# Display_CPu.net
KiCad netlist of a schematic drawn in Altium Designer
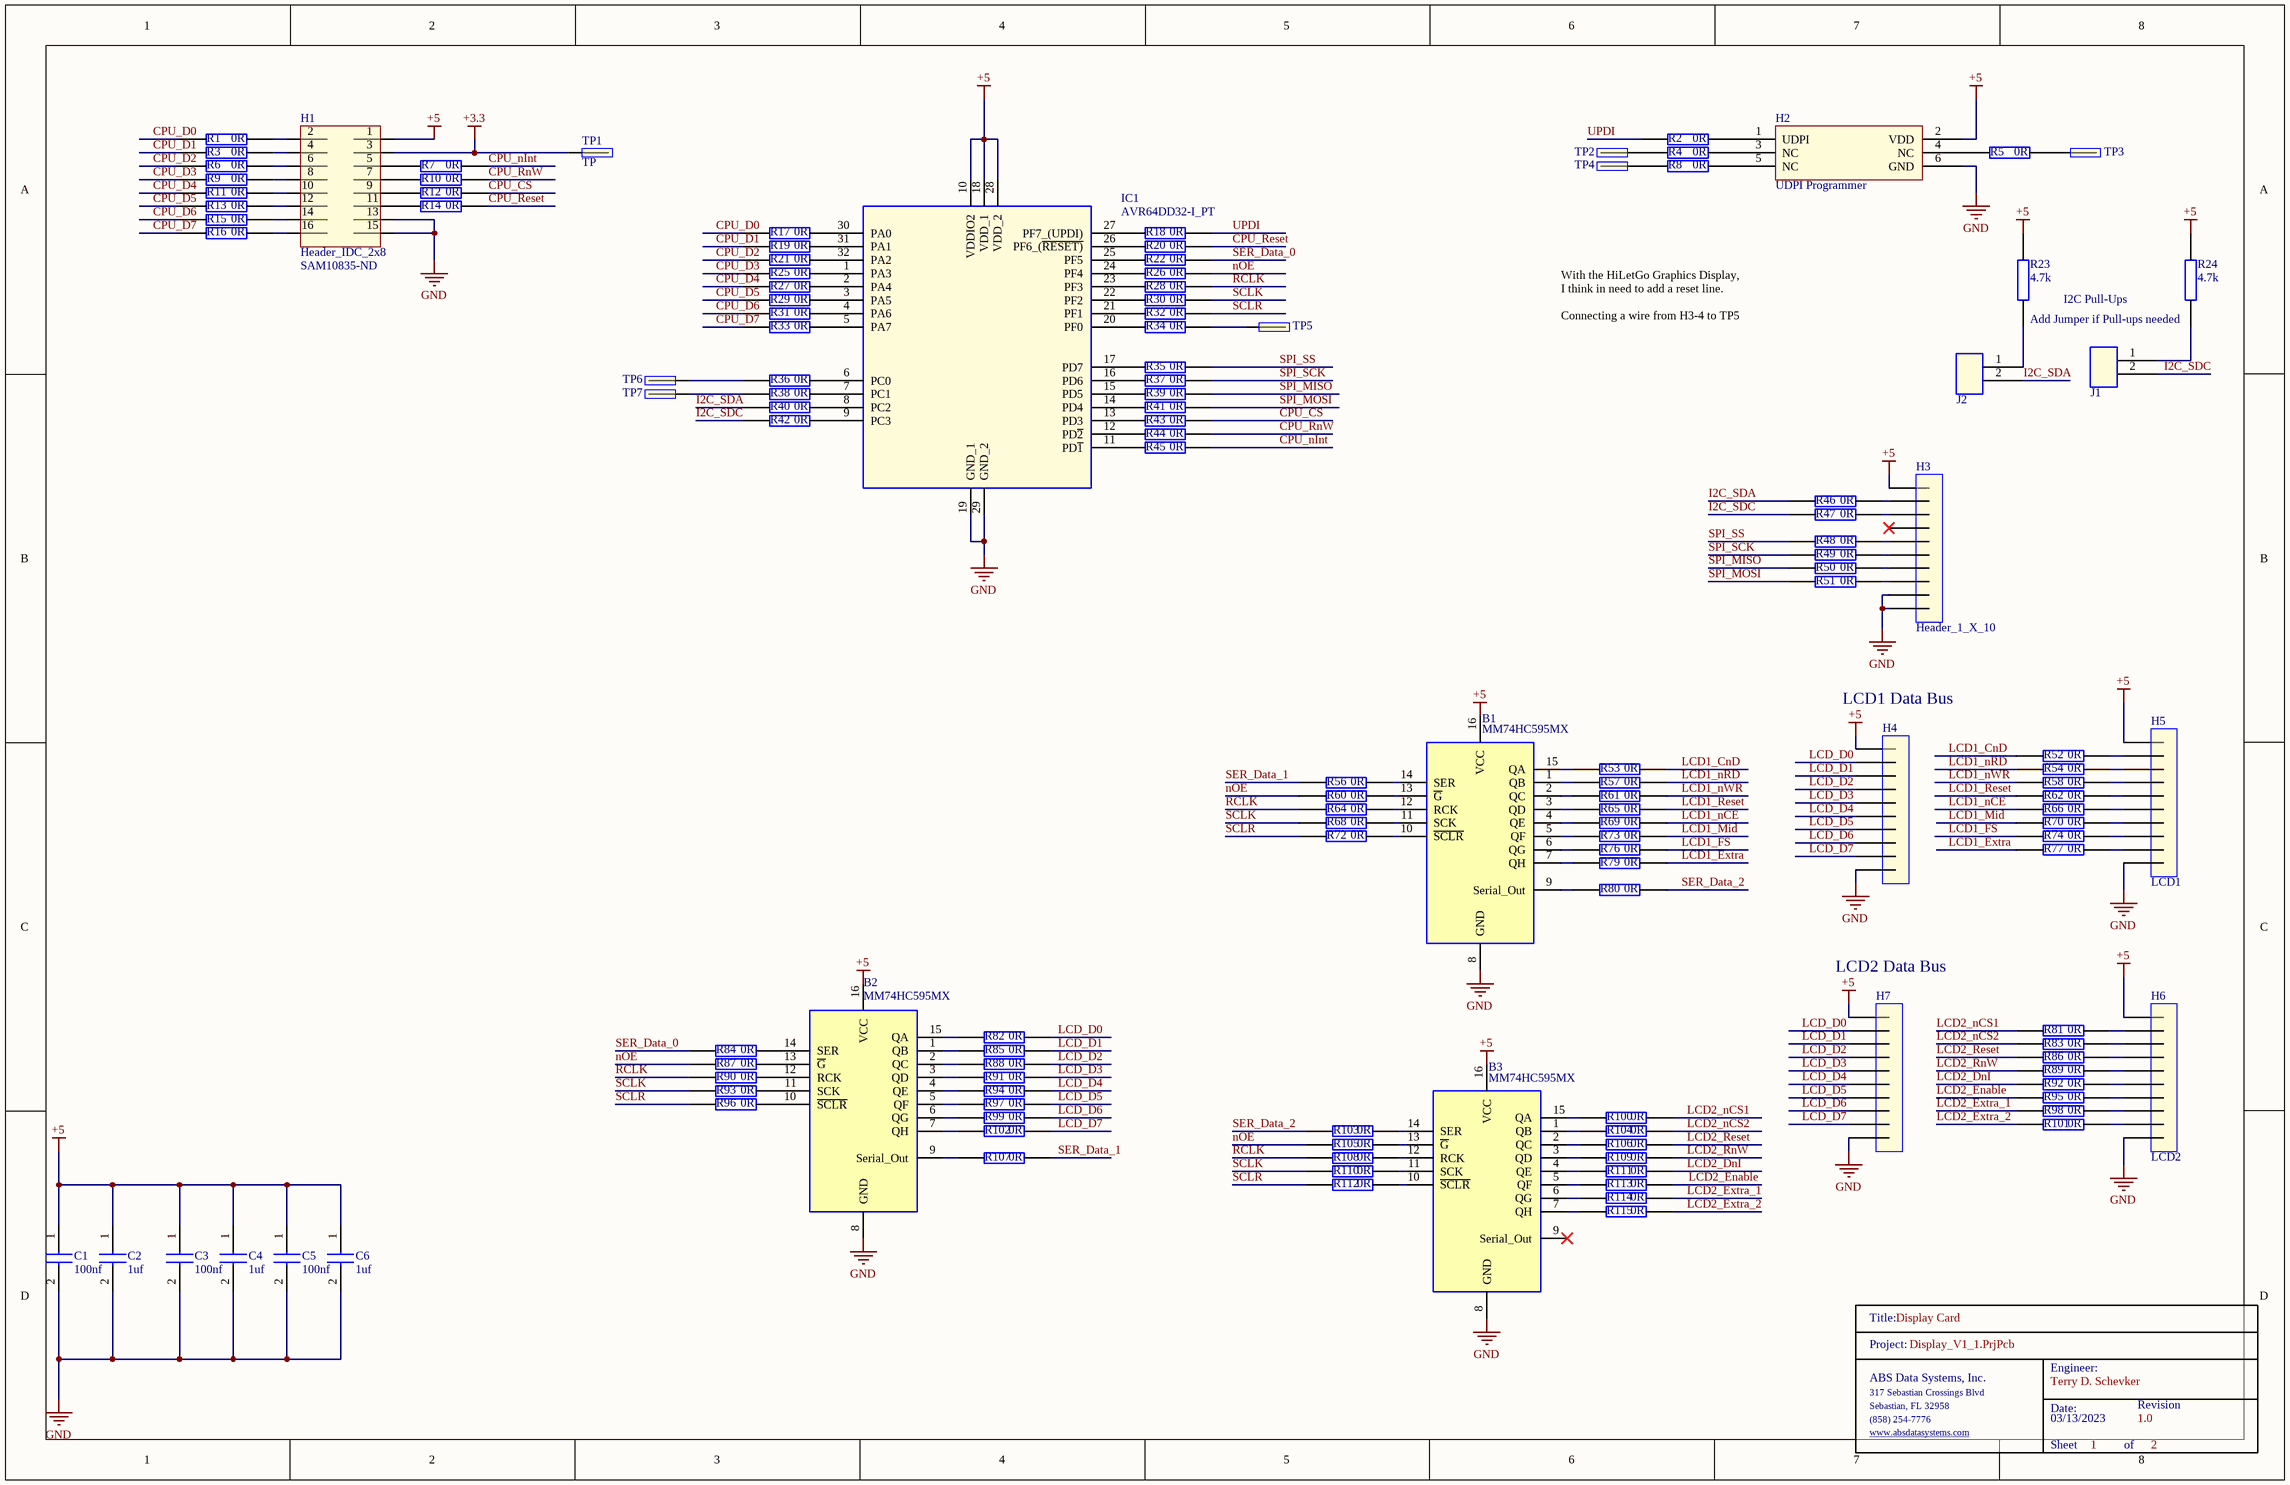
[diagram p0: Display_CPu.SchDoc]

(export (version "E")
  (design (tool "Eeschema 10.0.6"))
  (components
    (comp (ref "B1")
      (value "MM74HC595MX")
      (footprint "SOIC127P600X175-16N")
      (description "Shift Register HS 8 Bit CMOS SOIC16")
      (fields (field (name "MOUSER PART NUMBER") "512-MM74HC595MX"))
      (libsource (lib "SemiConductors") (part "MM74HC595MX"))
    )
    (comp (ref "B2")
      (value "MM74HC595MX")
      (footprint "SOIC127P600X175-16N")
      (description "Shift Register HS 8 Bit CMOS SOIC16")
      (fields (field (name "MOUSER PART NUMBER") "512-MM74HC595MX"))
      (libsource (lib "SemiConductors") (part "MM74HC595MX"))
    )
    (comp (ref "B3")
      (value "MM74HC595MX")
      (footprint "SOIC127P600X175-16N")
      (description "Shift Register HS 8 Bit CMOS SOIC16")
      (fields (field (name "MOUSER PART NUMBER") "512-MM74HC595MX"))
      (libsource (lib "SemiConductors") (part "MM74HC595MX"))
    )
    (comp (ref "C1")
      (value "100nf")
      (footprint "0603")
      (description "Samsung Electro-Mechanics 0603 100nf")
      (libsource (lib "Capacitors") (part "CL10B104JB8NNNC"))
    )
    (comp (ref "C2")
      (value "1uf")
      (footprint "0603")
      (description "Samsung Electro-Mechanics 0603 1uf")
      (libsource (lib "Capacitors") (part "CL10B105KA8NNNL"))
    )
    (comp (ref "C3")
      (value "100nf")
      (footprint "0603")
      (description "Samsung Electro-Mechanics 0603 100nf")
      (libsource (lib "Capacitors") (part "CL10B104JB8NNNC"))
    )
    (comp (ref "C4")
      (value "1uf")
      (footprint "0603")
      (description "Samsung Electro-Mechanics 0603 1uf")
      (libsource (lib "Capacitors") (part "CL10B105KA8NNNL"))
    )
    (comp (ref "C5")
      (value "100nf")
      (footprint "0603")
      (description "Samsung Electro-Mechanics 0603 100nf")
      (libsource (lib "Capacitors") (part "CL10B104JB8NNNC"))
    )
    (comp (ref "C6")
      (value "1uf")
      (footprint "0603")
      (description "Samsung Electro-Mechanics 0603 1uf")
      (libsource (lib "Capacitors") (part "CL10B105KA8NNNL"))
    )
    (comp (ref "H1")
      (value "Header_IDC_2x8")
      (footprint "HEADER16")
      (description "16 Pin 2x8 Through Hold IDC Connector")
      (fields
        (field (name "MANUFACTURER") "Samtec")
        (field (name "MANUFACTURER PART NUMBER") "TST-108-01-G-D")
        (field (name "SUPPLIER PART NUMBER 1") "SAM10835-ND")
      )
      (libsource (lib "Misc") (part "Header_IDC_2x8"))
    )
    (comp (ref "H2")
      (value "UDPI Programmer")
      (footprint "HDR2X3")
      (description "6 Pin 2X3 Through Hole Header")
      (libsource (lib "Misc") (part "UDPI Programmer"))
    )
    (comp (ref "H3")
      (value "Header_1_X_10")
      (footprint "TP_1X10")
      (fields
        (field (name "MANUFACTURER") "Samtec")
        (field (name "MANUFACTURER PART NUMBER") "TST-105-01-G-D")
      )
      (libsource (lib "Misc") (part "Header_1_X_10"))
    )
    (comp (ref "H4")
      (value "Header_1_X_10")
      (footprint "TP_1X10")
      (fields
        (field (name "MANUFACTURER") "Samtec")
        (field (name "MANUFACTURER PART NUMBER") "TST-105-01-G-D")
      )
      (libsource (lib "Misc") (part "Header_1_X_10"))
    )
    (comp (ref "H5")
      (value "LCD1")
      (footprint "TP_1X10")
      (fields
        (field (name "MANUFACTURER") "Samtec")
        (field (name "MANUFACTURER PART NUMBER") "TST-105-01-G-D")
      )
      (libsource (lib "Misc") (part "Header_1_X_10"))
    )
    (comp (ref "H6")
      (value "LCD2")
      (footprint "TP_1X10")
      (fields
        (field (name "MANUFACTURER") "Samtec")
        (field (name "MANUFACTURER PART NUMBER") "TST-105-01-G-D")
      )
      (libsource (lib "Misc") (part "Header_1_X_10"))
    )
    (comp (ref "H7")
      (value "Header_1_X_10")
      (footprint "TP_1X10")
      (fields
        (field (name "MANUFACTURER") "Samtec")
        (field (name "MANUFACTURER PART NUMBER") "TST-105-01-G-D")
      )
      (libsource (lib "Misc") (part "Header_1_X_10"))
    )
    (comp (ref "IC1")
      (value "AVR64DD32-I_PT")
      (footprint "CPU_Memory:QFP80P900X900X120-32N")
      (description "Integrated Circuit")
      (fields (field (name "MANUFACTURER_PART_NUMBER") "AVR64DD32-I/PT ¦ MULTI-VOLTAGE I/O"))
      (libsource (lib "CPU_Memory") (part "AVR64DD32-I_PT"))
    )
    (comp (ref "J1")
      (value "Jumper")
      (footprint "Jumper")
      (description "16 Pin 3x8 Through Hold Jumprts")
      (fields
        (field (name "MANUFACTURER") "Samtec")
        (field (name "MANUFACTURER PART NUMBER") "TST-108-01-G-D")
      )
      (libsource (lib "Misc") (part "Jumper"))
    )
    (comp (ref "J2")
      (value "Jumper")
      (footprint "Jumper")
      (description "16 Pin 3x8 Through Hold Jumprts")
      (fields
        (field (name "MANUFACTURER") "Samtec")
        (field (name "MANUFACTURER PART NUMBER") "TST-108-01-G-D")
      )
      (libsource (lib "Misc") (part "Jumper"))
    )
    (comp (ref "R1")
      (value "0R")
      (footprint "0603")
      (description "YAGEO 0603 0 ohm")
      (fields
        (field (name "MOUSER PART NUMBER") "603-RC0603JR-070RL")
        (field (name "MANUFACTURER_PART_NUMBER") "RC0603JR-070RL")
      )
      (libsource (lib "Resistors") (part "RC0603JR-070RL"))
    )
    (comp (ref "R2")
      (value "0R")
      (footprint "0603")
      (description "YAGEO 0603 0 ohm")
      (fields
        (field (name "MOUSER PART NUMBER") "603-RC0603JR-070RL")
        (field (name "MANUFACTURER_PART_NUMBER") "RC0603JR-070RL")
      )
      (libsource (lib "Resistors") (part "RC0603JR-070RL"))
    )
    (comp (ref "R3")
      (value "0R")
      (footprint "0603")
      (description "YAGEO 0603 0 ohm")
      (fields
        (field (name "MOUSER PART NUMBER") "603-RC0603JR-070RL")
        (field (name "MANUFACTURER_PART_NUMBER") "RC0603JR-070RL")
      )
      (libsource (lib "Resistors") (part "RC0603JR-070RL"))
    )
    (comp (ref "R4")
      (value "0R")
      (footprint "0603")
      (description "YAGEO 0603 0 ohm")
      (fields
        (field (name "MOUSER PART NUMBER") "603-RC0603JR-070RL")
        (field (name "MANUFACTURER_PART_NUMBER") "RC0603JR-070RL")
      )
      (libsource (lib "Resistors") (part "RC0603JR-070RL"))
    )
    (comp (ref "R5")
      (value "0R")
      (footprint "0603")
      (description "YAGEO 0603 0 ohm")
      (fields
        (field (name "MOUSER PART NUMBER") "603-RC0603JR-070RL")
        (field (name "MANUFACTURER_PART_NUMBER") "RC0603JR-070RL")
      )
      (libsource (lib "Resistors") (part "RC0603JR-070RL"))
    )
    (comp (ref "R6")
      (value "0R")
      (footprint "0603")
      (description "YAGEO 0603 0 ohm")
      (fields
        (field (name "MOUSER PART NUMBER") "603-RC0603JR-070RL")
        (field (name "MANUFACTURER_PART_NUMBER") "RC0603JR-070RL")
      )
      (libsource (lib "Resistors") (part "RC0603JR-070RL"))
    )
    (comp (ref "R7")
      (value "0R")
      (footprint "0603")
      (description "YAGEO 0603 0 ohm")
      (fields
        (field (name "MOUSER PART NUMBER") "603-RC0603JR-070RL")
        (field (name "MANUFACTURER_PART_NUMBER") "RC0603JR-070RL")
      )
      (libsource (lib "Resistors") (part "RC0603JR-070RL"))
    )
    (comp (ref "R8")
      (value "0R")
      (footprint "0603")
      (description "YAGEO 0603 0 ohm")
      (fields
        (field (name "MOUSER PART NUMBER") "603-RC0603JR-070RL")
        (field (name "MANUFACTURER_PART_NUMBER") "RC0603JR-070RL")
      )
      (libsource (lib "Resistors") (part "RC0603JR-070RL"))
    )
    (comp (ref "R9")
      (value "0R")
      (footprint "0603")
      (description "YAGEO 0603 0 ohm")
      (fields
        (field (name "MOUSER PART NUMBER") "603-RC0603JR-070RL")
        (field (name "MANUFACTURER_PART_NUMBER") "RC0603JR-070RL")
      )
      (libsource (lib "Resistors") (part "RC0603JR-070RL"))
    )
    (comp (ref "R10")
      (value "0R")
      (footprint "0603")
      (description "YAGEO 0603 0 ohm")
      (fields
        (field (name "MOUSER PART NUMBER") "603-RC0603JR-070RL")
        (field (name "MANUFACTURER_PART_NUMBER") "RC0603JR-070RL")
      )
      (libsource (lib "Resistors") (part "RC0603JR-070RL"))
    )
    (comp (ref "R11")
      (value "0R")
      (footprint "0603")
      (description "YAGEO 0603 0 ohm")
      (fields
        (field (name "MOUSER PART NUMBER") "603-RC0603JR-070RL")
        (field (name "MANUFACTURER_PART_NUMBER") "RC0603JR-070RL")
      )
      (libsource (lib "Resistors") (part "RC0603JR-070RL"))
    )
    (comp (ref "R12")
      (value "0R")
      (footprint "0603")
      (description "YAGEO 0603 0 ohm")
      (fields
        (field (name "MOUSER PART NUMBER") "603-RC0603JR-070RL")
        (field (name "MANUFACTURER_PART_NUMBER") "RC0603JR-070RL")
      )
      (libsource (lib "Resistors") (part "RC0603JR-070RL"))
    )
    (comp (ref "R13")
      (value "0R")
      (footprint "0603")
      (description "YAGEO 0603 0 ohm")
      (fields
        (field (name "MOUSER PART NUMBER") "603-RC0603JR-070RL")
        (field (name "MANUFACTURER_PART_NUMBER") "RC0603JR-070RL")
      )
      (libsource (lib "Resistors") (part "RC0603JR-070RL"))
    )
    (comp (ref "R14")
      (value "0R")
      (footprint "0603")
      (description "YAGEO 0603 0 ohm")
      (fields
        (field (name "MOUSER PART NUMBER") "603-RC0603JR-070RL")
        (field (name "MANUFACTURER_PART_NUMBER") "RC0603JR-070RL")
      )
      (libsource (lib "Resistors") (part "RC0603JR-070RL"))
    )
    (comp (ref "R15")
      (value "0R")
      (footprint "0603")
      (description "YAGEO 0603 0 ohm")
      (fields
        (field (name "MOUSER PART NUMBER") "603-RC0603JR-070RL")
        (field (name "MANUFACTURER_PART_NUMBER") "RC0603JR-070RL")
      )
      (libsource (lib "Resistors") (part "RC0603JR-070RL"))
    )
    (comp (ref "R16")
      (value "0R")
      (footprint "0603")
      (description "YAGEO 0603 0 ohm")
      (fields
        (field (name "MOUSER PART NUMBER") "603-RC0603JR-070RL")
        (field (name "MANUFACTURER_PART_NUMBER") "RC0603JR-070RL")
      )
      (libsource (lib "Resistors") (part "RC0603JR-070RL"))
    )
    (comp (ref "R17")
      (value "0R")
      (footprint "0603")
      (description "YAGEO 0603 0 ohm")
      (fields
        (field (name "MOUSER PART NUMBER") "603-RC0603JR-070RL")
        (field (name "MANUFACTURER_PART_NUMBER") "RC0603JR-070RL")
      )
      (libsource (lib "Resistors") (part "RC0603JR-070RL"))
    )
    (comp (ref "R18")
      (value "0R")
      (footprint "0603")
      (description "YAGEO 0603 0 ohm")
      (fields
        (field (name "MOUSER PART NUMBER") "603-RC0603JR-070RL")
        (field (name "MANUFACTURER_PART_NUMBER") "RC0603JR-070RL")
      )
      (libsource (lib "Resistors") (part "RC0603JR-070RL"))
    )
    (comp (ref "R19")
      (value "0R")
      (footprint "0603")
      (description "YAGEO 0603 0 ohm")
      (fields
        (field (name "MOUSER PART NUMBER") "603-RC0603JR-070RL")
        (field (name "MANUFACTURER_PART_NUMBER") "RC0603JR-070RL")
      )
      (libsource (lib "Resistors") (part "RC0603JR-070RL"))
    )
    (comp (ref "R20")
      (value "0R")
      (footprint "0603")
      (description "YAGEO 0603 0 ohm")
      (fields
        (field (name "MOUSER PART NUMBER") "603-RC0603JR-070RL")
        (field (name "MANUFACTURER_PART_NUMBER") "RC0603JR-070RL")
      )
      (libsource (lib "Resistors") (part "RC0603JR-070RL"))
    )
    (comp (ref "R21")
      (value "0R")
      (footprint "0603")
      (description "YAGEO 0603 0 ohm")
      (fields
        (field (name "MOUSER PART NUMBER") "603-RC0603JR-070RL")
        (field (name "MANUFACTURER_PART_NUMBER") "RC0603JR-070RL")
      )
      (libsource (lib "Resistors") (part "RC0603JR-070RL"))
    )
    (comp (ref "R22")
      (value "0R")
      (footprint "0603")
      (description "YAGEO 0603 0 ohm")
      (fields
        (field (name "MOUSER PART NUMBER") "603-RC0603JR-070RL")
        (field (name "MANUFACTURER_PART_NUMBER") "RC0603JR-070RL")
      )
      (libsource (lib "Resistors") (part "RC0603JR-070RL"))
    )
    (comp (ref "R23")
      (value "4.7k")
      (footprint "0603")
      (description "YAGEO 0603 4.7k")
      (fields
        (field (name "MOUSER PART NUMBER") "603-RC0603JR-070RL")
        (field (name "MANUFACTURER_PART_NUMBER") "RC0603JR-070RL")
      )
      (libsource (lib "Resistors") (part "RC0603FR-104K7L"))
    )
    (comp (ref "R24")
      (value "4.7k")
      (footprint "0603")
      (description "YAGEO 0603 4.7k")
      (fields
        (field (name "MOUSER PART NUMBER") "603-RC0603JR-070RL")
        (field (name "MANUFACTURER_PART_NUMBER") "RC0603JR-070RL")
      )
      (libsource (lib "Resistors") (part "RC0603FR-104K7L"))
    )
    (comp (ref "R25")
      (value "0R")
      (footprint "0603")
      (description "YAGEO 0603 0 ohm")
      (fields
        (field (name "MOUSER PART NUMBER") "603-RC0603JR-070RL")
        (field (name "MANUFACTURER_PART_NUMBER") "RC0603JR-070RL")
      )
      (libsource (lib "Resistors") (part "RC0603JR-070RL"))
    )
    (comp (ref "R26")
      (value "0R")
      (footprint "0603")
      (description "YAGEO 0603 0 ohm")
      (fields
        (field (name "MOUSER PART NUMBER") "603-RC0603JR-070RL")
        (field (name "MANUFACTURER_PART_NUMBER") "RC0603JR-070RL")
      )
      (libsource (lib "Resistors") (part "RC0603JR-070RL"))
    )
    (comp (ref "R27")
      (value "0R")
      (footprint "0603")
      (description "YAGEO 0603 0 ohm")
      (fields
        (field (name "MOUSER PART NUMBER") "603-RC0603JR-070RL")
        (field (name "MANUFACTURER_PART_NUMBER") "RC0603JR-070RL")
      )
      (libsource (lib "Resistors") (part "RC0603JR-070RL"))
    )
    (comp (ref "R28")
      (value "0R")
      (footprint "0603")
      (description "YAGEO 0603 0 ohm")
      (fields
        (field (name "MOUSER PART NUMBER") "603-RC0603JR-070RL")
        (field (name "MANUFACTURER_PART_NUMBER") "RC0603JR-070RL")
      )
      (libsource (lib "Resistors") (part "RC0603JR-070RL"))
    )
    (comp (ref "R29")
      (value "0R")
      (footprint "0603")
      (description "YAGEO 0603 0 ohm")
      (fields
        (field (name "MOUSER PART NUMBER") "603-RC0603JR-070RL")
        (field (name "MANUFACTURER_PART_NUMBER") "RC0603JR-070RL")
      )
      (libsource (lib "Resistors") (part "RC0603JR-070RL"))
    )
    (comp (ref "R30")
      (value "0R")
      (footprint "0603")
      (description "YAGEO 0603 0 ohm")
      (fields
        (field (name "MOUSER PART NUMBER") "603-RC0603JR-070RL")
        (field (name "MANUFACTURER_PART_NUMBER") "RC0603JR-070RL")
      )
      (libsource (lib "Resistors") (part "RC0603JR-070RL"))
    )
    (comp (ref "R31")
      (value "0R")
      (footprint "0603")
      (description "YAGEO 0603 0 ohm")
      (fields
        (field (name "MOUSER PART NUMBER") "603-RC0603JR-070RL")
        (field (name "MANUFACTURER_PART_NUMBER") "RC0603JR-070RL")
      )
      (libsource (lib "Resistors") (part "RC0603JR-070RL"))
    )
    (comp (ref "R32")
      (value "0R")
      (footprint "0603")
      (description "YAGEO 0603 0 ohm")
      (fields
        (field (name "MOUSER PART NUMBER") "603-RC0603JR-070RL")
        (field (name "MANUFACTURER_PART_NUMBER") "RC0603JR-070RL")
      )
      (libsource (lib "Resistors") (part "RC0603JR-070RL"))
    )
    (comp (ref "R33")
      (value "0R")
      (footprint "0603")
      (description "YAGEO 0603 0 ohm")
      (fields
        (field (name "MOUSER PART NUMBER") "603-RC0603JR-070RL")
        (field (name "MANUFACTURER_PART_NUMBER") "RC0603JR-070RL")
      )
      (libsource (lib "Resistors") (part "RC0603JR-070RL"))
    )
    (comp (ref "R34")
      (value "0R")
      (footprint "0603")
      (description "YAGEO 0603 0 ohm")
      (fields
        (field (name "MOUSER PART NUMBER") "603-RC0603JR-070RL")
        (field (name "MANUFACTURER_PART_NUMBER") "RC0603JR-070RL")
      )
      (libsource (lib "Resistors") (part "RC0603JR-070RL"))
    )
    (comp (ref "R35")
      (value "0R")
      (footprint "0603")
      (description "YAGEO 0603 0 ohm")
      (fields
        (field (name "MOUSER PART NUMBER") "603-RC0603JR-070RL")
        (field (name "MANUFACTURER_PART_NUMBER") "RC0603JR-070RL")
      )
      (libsource (lib "Resistors") (part "RC0603JR-070RL"))
    )
    (comp (ref "R36")
      (value "0R")
      (footprint "0603")
      (description "YAGEO 0603 0 ohm")
      (fields
        (field (name "MOUSER PART NUMBER") "603-RC0603JR-070RL")
        (field (name "MANUFACTURER_PART_NUMBER") "RC0603JR-070RL")
      )
      (libsource (lib "Resistors") (part "RC0603JR-070RL"))
    )
    (comp (ref "R37")
      (value "0R")
      (footprint "0603")
      (description "YAGEO 0603 0 ohm")
      (fields
        (field (name "MOUSER PART NUMBER") "603-RC0603JR-070RL")
        (field (name "MANUFACTURER_PART_NUMBER") "RC0603JR-070RL")
      )
      (libsource (lib "Resistors") (part "RC0603JR-070RL"))
    )
    (comp (ref "R38")
      (value "0R")
      (footprint "0603")
      (description "YAGEO 0603 0 ohm")
      (fields
        (field (name "MOUSER PART NUMBER") "603-RC0603JR-070RL")
        (field (name "MANUFACTURER_PART_NUMBER") "RC0603JR-070RL")
      )
      (libsource (lib "Resistors") (part "RC0603JR-070RL"))
    )
    (comp (ref "R39")
      (value "0R")
      (footprint "0603")
      (description "YAGEO 0603 0 ohm")
      (fields
        (field (name "MOUSER PART NUMBER") "603-RC0603JR-070RL")
        (field (name "MANUFACTURER_PART_NUMBER") "RC0603JR-070RL")
      )
      (libsource (lib "Resistors") (part "RC0603JR-070RL"))
    )
    (comp (ref "R40")
      (value "0R")
      (footprint "0603")
      (description "YAGEO 0603 0 ohm")
      (fields
        (field (name "MOUSER PART NUMBER") "603-RC0603JR-070RL")
        (field (name "MANUFACTURER_PART_NUMBER") "RC0603JR-070RL")
      )
      (libsource (lib "Resistors") (part "RC0603JR-070RL"))
    )
    (comp (ref "R41")
      (value "0R")
      (footprint "0603")
      (description "YAGEO 0603 0 ohm")
      (fields
        (field (name "MOUSER PART NUMBER") "603-RC0603JR-070RL")
        (field (name "MANUFACTURER_PART_NUMBER") "RC0603JR-070RL")
      )
      (libsource (lib "Resistors") (part "RC0603JR-070RL"))
    )
    (comp (ref "R42")
      (value "0R")
      (footprint "0603")
      (description "YAGEO 0603 0 ohm")
      (fields
        (field (name "MOUSER PART NUMBER") "603-RC0603JR-070RL")
        (field (name "MANUFACTURER_PART_NUMBER") "RC0603JR-070RL")
      )
      (libsource (lib "Resistors") (part "RC0603JR-070RL"))
    )
    (comp (ref "R43")
      (value "0R")
      (footprint "0603")
      (description "YAGEO 0603 0 ohm")
      (fields
        (field (name "MOUSER PART NUMBER") "603-RC0603JR-070RL")
        (field (name "MANUFACTURER_PART_NUMBER") "RC0603JR-070RL")
      )
      (libsource (lib "Resistors") (part "RC0603JR-070RL"))
    )
    (comp (ref "R44")
      (value "0R")
      (footprint "0603")
      (description "YAGEO 0603 0 ohm")
      (fields
        (field (name "MOUSER PART NUMBER") "603-RC0603JR-070RL")
        (field (name "MANUFACTURER_PART_NUMBER") "RC0603JR-070RL")
      )
      (libsource (lib "Resistors") (part "RC0603JR-070RL"))
    )
    (comp (ref "R45")
      (value "0R")
      (footprint "0603")
      (description "YAGEO 0603 0 ohm")
      (fields
        (field (name "MOUSER PART NUMBER") "603-RC0603JR-070RL")
        (field (name "MANUFACTURER_PART_NUMBER") "RC0603JR-070RL")
      )
      (libsource (lib "Resistors") (part "RC0603JR-070RL"))
    )
    (comp (ref "R46")
      (value "0R")
      (footprint "0603")
      (description "YAGEO 0603 0 ohm")
      (fields
        (field (name "MOUSER PART NUMBER") "603-RC0603JR-070RL")
        (field (name "MANUFACTURER_PART_NUMBER") "RC0603JR-070RL")
      )
      (libsource (lib "Resistors") (part "RC0603JR-070RL"))
    )
    (comp (ref "R47")
      (value "0R")
      (footprint "0603")
      (description "YAGEO 0603 0 ohm")
      (fields
        (field (name "MOUSER PART NUMBER") "603-RC0603JR-070RL")
        (field (name "MANUFACTURER_PART_NUMBER") "RC0603JR-070RL")
      )
      (libsource (lib "Resistors") (part "RC0603JR-070RL"))
    )
    (comp (ref "R48")
      (value "0R")
      (footprint "0603")
      (description "YAGEO 0603 0 ohm")
      (fields
        (field (name "MOUSER PART NUMBER") "603-RC0603JR-070RL")
        (field (name "MANUFACTURER_PART_NUMBER") "RC0603JR-070RL")
      )
      (libsource (lib "Resistors") (part "RC0603JR-070RL"))
    )
    (comp (ref "R49")
      (value "0R")
      (footprint "0603")
      (description "YAGEO 0603 0 ohm")
      (fields
        (field (name "MOUSER PART NUMBER") "603-RC0603JR-070RL")
        (field (name "MANUFACTURER_PART_NUMBER") "RC0603JR-070RL")
      )
      (libsource (lib "Resistors") (part "RC0603JR-070RL"))
    )
    (comp (ref "R50")
      (value "0R")
      (footprint "0603")
      (description "YAGEO 0603 0 ohm")
      (fields
        (field (name "MOUSER PART NUMBER") "603-RC0603JR-070RL")
        (field (name "MANUFACTURER_PART_NUMBER") "RC0603JR-070RL")
      )
      (libsource (lib "Resistors") (part "RC0603JR-070RL"))
    )
    (comp (ref "R51")
      (value "0R")
      (footprint "0603")
      (description "YAGEO 0603 0 ohm")
      (fields
        (field (name "MOUSER PART NUMBER") "603-RC0603JR-070RL")
        (field (name "MANUFACTURER_PART_NUMBER") "RC0603JR-070RL")
      )
      (libsource (lib "Resistors") (part "RC0603JR-070RL"))
    )
    (comp (ref "R52")
      (value "0R")
      (footprint "0603")
      (description "YAGEO 0603 0 ohm")
      (fields
        (field (name "MOUSER PART NUMBER") "603-RC0603JR-070RL")
        (field (name "MANUFACTURER_PART_NUMBER") "RC0603JR-070RL")
      )
      (libsource (lib "Resistors") (part "RC0603JR-070RL"))
    )
    (comp (ref "R53")
      (value "0R")
      (footprint "0603")
      (description "YAGEO 0603 0 ohm")
      (fields
        (field (name "MOUSER PART NUMBER") "603-RC0603JR-070RL")
        (field (name "MANUFACTURER_PART_NUMBER") "RC0603JR-070RL")
      )
      (libsource (lib "Resistors") (part "RC0603JR-070RL"))
    )
    (comp (ref "R54")
      (value "0R")
      (footprint "0603")
      (description "YAGEO 0603 0 ohm")
      (fields
        (field (name "MOUSER PART NUMBER") "603-RC0603JR-070RL")
        (field (name "MANUFACTURER_PART_NUMBER") "RC0603JR-070RL")
      )
      (libsource (lib "Resistors") (part "RC0603JR-070RL"))
    )
    (comp (ref "R56")
      (value "0R")
      (footprint "0603")
      (description "YAGEO 0603 0 ohm")
      (fields
        (field (name "MOUSER PART NUMBER") "603-RC0603JR-070RL")
        (field (name "MANUFACTURER_PART_NUMBER") "RC0603JR-070RL")
      )
      (libsource (lib "Resistors") (part "RC0603JR-070RL"))
    )
    (comp (ref "R57")
      (value "0R")
      (footprint "0603")
      (description "YAGEO 0603 0 ohm")
      (fields
        (field (name "MOUSER PART NUMBER") "603-RC0603JR-070RL")
        (field (name "MANUFACTURER_PART_NUMBER") "RC0603JR-070RL")
      )
      (libsource (lib "Resistors") (part "RC0603JR-070RL"))
    )
    (comp (ref "R58")
      (value "0R")
      (footprint "0603")
      (description "YAGEO 0603 0 ohm")
      (fields
        (field (name "MOUSER PART NUMBER") "603-RC0603JR-070RL")
        (field (name "MANUFACTURER_PART_NUMBER") "RC0603JR-070RL")
      )
      (libsource (lib "Resistors") (part "RC0603JR-070RL"))
    )
    (comp (ref "R60")
      (value "0R")
      (footprint "0603")
      (description "YAGEO 0603 0 ohm")
      (fields
        (field (name "MOUSER PART NUMBER") "603-RC0603JR-070RL")
        (field (name "MANUFACTURER_PART_NUMBER") "RC0603JR-070RL")
      )
      (libsource (lib "Resistors") (part "RC0603JR-070RL"))
    )
    (comp (ref "R61")
      (value "0R")
      (footprint "0603")
      (description "YAGEO 0603 0 ohm")
      (fields
        (field (name "MOUSER PART NUMBER") "603-RC0603JR-070RL")
        (field (name "MANUFACTURER_PART_NUMBER") "RC0603JR-070RL")
      )
      (libsource (lib "Resistors") (part "RC0603JR-070RL"))
    )
    (comp (ref "R62")
      (value "0R")
      (footprint "0603")
      (description "YAGEO 0603 0 ohm")
      (fields
        (field (name "MOUSER PART NUMBER") "603-RC0603JR-070RL")
        (field (name "MANUFACTURER_PART_NUMBER") "RC0603JR-070RL")
      )
      (libsource (lib "Resistors") (part "RC0603JR-070RL"))
    )
    (comp (ref "R64")
      (value "0R")
      (footprint "0603")
      (description "YAGEO 0603 0 ohm")
      (fields
        (field (name "MOUSER PART NUMBER") "603-RC0603JR-070RL")
        (field (name "MANUFACTURER_PART_NUMBER") "RC0603JR-070RL")
      )
      (libsource (lib "Resistors") (part "RC0603JR-070RL"))
    )
    (comp (ref "R65")
      (value "0R")
      (footprint "0603")
      (description "YAGEO 0603 0 ohm")
      (fields
        (field (name "MOUSER PART NUMBER") "603-RC0603JR-070RL")
        (field (name "MANUFACTURER_PART_NUMBER") "RC0603JR-070RL")
      )
      (libsource (lib "Resistors") (part "RC0603JR-070RL"))
    )
    (comp (ref "R66")
      (value "0R")
      (footprint "0603")
      (description "YAGEO 0603 0 ohm")
      (fields
        (field (name "MOUSER PART NUMBER") "603-RC0603JR-070RL")
        (field (name "MANUFACTURER_PART_NUMBER") "RC0603JR-070RL")
      )
      (libsource (lib "Resistors") (part "RC0603JR-070RL"))
    )
    (comp (ref "R68")
      (value "0R")
      (footprint "0603")
      (description "YAGEO 0603 0 ohm")
      (fields
        (field (name "MOUSER PART NUMBER") "603-RC0603JR-070RL")
        (field (name "MANUFACTURER_PART_NUMBER") "RC0603JR-070RL")
      )
      (libsource (lib "Resistors") (part "RC0603JR-070RL"))
    )
    (comp (ref "R69")
      (value "0R")
      (footprint "0603")
      (description "YAGEO 0603 0 ohm")
      (fields
        (field (name "MOUSER PART NUMBER") "603-RC0603JR-070RL")
        (field (name "MANUFACTURER_PART_NUMBER") "RC0603JR-070RL")
      )
      (libsource (lib "Resistors") (part "RC0603JR-070RL"))
    )
    (comp (ref "R70")
      (value "0R")
      (footprint "0603")
      (description "YAGEO 0603 0 ohm")
      (fields
        (field (name "MOUSER PART NUMBER") "603-RC0603JR-070RL")
        (field (name "MANUFACTURER_PART_NUMBER") "RC0603JR-070RL")
      )
      (libsource (lib "Resistors") (part "RC0603JR-070RL"))
    )
    (comp (ref "R72")
      (value "0R")
      (footprint "0603")
      (description "YAGEO 0603 0 ohm")
      (fields
        (field (name "MOUSER PART NUMBER") "603-RC0603JR-070RL")
        (field (name "MANUFACTURER_PART_NUMBER") "RC0603JR-070RL")
      )
      (libsource (lib "Resistors") (part "RC0603JR-070RL"))
    )
    (comp (ref "R73")
      (value "0R")
      (footprint "0603")
      (description "YAGEO 0603 0 ohm")
      (fields
        (field (name "MOUSER PART NUMBER") "603-RC0603JR-070RL")
        (field (name "MANUFACTURER_PART_NUMBER") "RC0603JR-070RL")
      )
      (libsource (lib "Resistors") (part "RC0603JR-070RL"))
    )
    (comp (ref "R74")
      (value "0R")
      (footprint "0603")
      (description "YAGEO 0603 0 ohm")
      (fields
        (field (name "MOUSER PART NUMBER") "603-RC0603JR-070RL")
        (field (name "MANUFACTURER_PART_NUMBER") "RC0603JR-070RL")
      )
      (libsource (lib "Resistors") (part "RC0603JR-070RL"))
    )
    (comp (ref "R76")
      (value "0R")
      (footprint "0603")
      (description "YAGEO 0603 0 ohm")
      (fields
        (field (name "MOUSER PART NUMBER") "603-RC0603JR-070RL")
        (field (name "MANUFACTURER_PART_NUMBER") "RC0603JR-070RL")
      )
      (libsource (lib "Resistors") (part "RC0603JR-070RL"))
    )
    (comp (ref "R77")
      (value "0R")
      (footprint "0603")
      (description "YAGEO 0603 0 ohm")
      (fields
        (field (name "MOUSER PART NUMBER") "603-RC0603JR-070RL")
        (field (name "MANUFACTURER_PART_NUMBER") "RC0603JR-070RL")
      )
      (libsource (lib "Resistors") (part "RC0603JR-070RL"))
    )
    (comp (ref "R79")
      (value "0R")
      (footprint "0603")
      (description "YAGEO 0603 0 ohm")
      (fields
        (field (name "MOUSER PART NUMBER") "603-RC0603JR-070RL")
        (field (name "MANUFACTURER_PART_NUMBER") "RC0603JR-070RL")
      )
      (libsource (lib "Resistors") (part "RC0603JR-070RL"))
    )
    (comp (ref "R80")
      (value "0R")
      (footprint "0603")
      (description "YAGEO 0603 0 ohm")
      (fields
        (field (name "MOUSER PART NUMBER") "603-RC0603JR-070RL")
        (field (name "MANUFACTURER_PART_NUMBER") "RC0603JR-070RL")
      )
      (libsource (lib "Resistors") (part "RC0603JR-070RL"))
    )
    (comp (ref "R81")
      (value "0R")
      (footprint "0603")
      (description "YAGEO 0603 0 ohm")
      (fields
        (field (name "MOUSER PART NUMBER") "603-RC0603JR-070RL")
        (field (name "MANUFACTURER_PART_NUMBER") "RC0603JR-070RL")
      )
      (libsource (lib "Resistors") (part "RC0603JR-070RL"))
    )
    (comp (ref "R82")
      (value "0R")
      (footprint "0603")
      (description "YAGEO 0603 0 ohm")
      (fields
        (field (name "MOUSER PART NUMBER") "603-RC0603JR-070RL")
        (field (name "MANUFACTURER_PART_NUMBER") "RC0603JR-070RL")
      )
      (libsource (lib "Resistors") (part "RC0603JR-070RL"))
    )
    (comp (ref "R83")
      (value "0R")
      (footprint "0603")
      (description "YAGEO 0603 0 ohm")
      (fields
        (field (name "MOUSER PART NUMBER") "603-RC0603JR-070RL")
        (field (name "MANUFACTURER_PART_NUMBER") "RC0603JR-070RL")
      )
      (libsource (lib "Resistors") (part "RC0603JR-070RL"))
    )
    (comp (ref "R84")
      (value "0R")
      (footprint "0603")
      (description "YAGEO 0603 0 ohm")
      (fields
        (field (name "MOUSER PART NUMBER") "603-RC0603JR-070RL")
        (field (name "MANUFACTURER_PART_NUMBER") "RC0603JR-070RL")
      )
      (libsource (lib "Resistors") (part "RC0603JR-070RL"))
    )
    (comp (ref "R85")
      (value "0R")
      (footprint "0603")
      (description "YAGEO 0603 0 ohm")
      (fields
        (field (name "MOUSER PART NUMBER") "603-RC0603JR-070RL")
        (field (name "MANUFACTURER_PART_NUMBER") "RC0603JR-070RL")
      )
      (libsource (lib "Resistors") (part "RC0603JR-070RL"))
    )
    (comp (ref "R86")
      (value "0R")
      (footprint "0603")
      (description "YAGEO 0603 0 ohm")
      (fields
        (field (name "MOUSER PART NUMBER") "603-RC0603JR-070RL")
        (field (name "MANUFACTURER_PART_NUMBER") "RC0603JR-070RL")
      )
      (libsource (lib "Resistors") (part "RC0603JR-070RL"))
    )
    (comp (ref "R87")
      (value "0R")
      (footprint "0603")
      (description "YAGEO 0603 0 ohm")
      (fields
        (field (name "MOUSER PART NUMBER") "603-RC0603JR-070RL")
        (field (name "MANUFACTURER_PART_NUMBER") "RC0603JR-070RL")
      )
      (libsource (lib "Resistors") (part "RC0603JR-070RL"))
    )
    (comp (ref "R88")
      (value "0R")
      (footprint "0603")
      (description "YAGEO 0603 0 ohm")
      (fields
        (field (name "MOUSER PART NUMBER") "603-RC0603JR-070RL")
        (field (name "MANUFACTURER_PART_NUMBER") "RC0603JR-070RL")
      )
      (libsource (lib "Resistors") (part "RC0603JR-070RL"))
    )
    (comp (ref "R89")
      (value "0R")
      (footprint "0603")
      (description "YAGEO 0603 0 ohm")
      (fields
        (field (name "MOUSER PART NUMBER") "603-RC0603JR-070RL")
        (field (name "MANUFACTURER_PART_NUMBER") "RC0603JR-070RL")
      )
      (libsource (lib "Resistors") (part "RC0603JR-070RL"))
    )
    (comp (ref "R90")
      (value "0R")
      (footprint "0603")
      (description "YAGEO 0603 0 ohm")
      (fields
        (field (name "MOUSER PART NUMBER") "603-RC0603JR-070RL")
        (field (name "MANUFACTURER_PART_NUMBER") "RC0603JR-070RL")
      )
      (libsource (lib "Resistors") (part "RC0603JR-070RL"))
    )
    (comp (ref "R91")
      (value "0R")
      (footprint "0603")
      (description "YAGEO 0603 0 ohm")
      (fields
        (field (name "MOUSER PART NUMBER") "603-RC0603JR-070RL")
        (field (name "MANUFACTURER_PART_NUMBER") "RC0603JR-070RL")
      )
      (libsource (lib "Resistors") (part "RC0603JR-070RL"))
    )
    (comp (ref "R92")
      (value "0R")
      (footprint "0603")
      (description "YAGEO 0603 0 ohm")
      (fields
        (field (name "MOUSER PART NUMBER") "603-RC0603JR-070RL")
        (field (name "MANUFACTURER_PART_NUMBER") "RC0603JR-070RL")
      )
      (libsource (lib "Resistors") (part "RC0603JR-070RL"))
    )
    (comp (ref "R93")
      (value "0R")
      (footprint "0603")
      (description "YAGEO 0603 0 ohm")
      (fields
        (field (name "MOUSER PART NUMBER") "603-RC0603JR-070RL")
        (field (name "MANUFACTURER_PART_NUMBER") "RC0603JR-070RL")
      )
      (libsource (lib "Resistors") (part "RC0603JR-070RL"))
    )
    (comp (ref "R94")
      (value "0R")
      (footprint "0603")
      (description "YAGEO 0603 0 ohm")
      (fields
        (field (name "MOUSER PART NUMBER") "603-RC0603JR-070RL")
        (field (name "MANUFACTURER_PART_NUMBER") "RC0603JR-070RL")
      )
      (libsource (lib "Resistors") (part "RC0603JR-070RL"))
    )
    (comp (ref "R95")
      (value "0R")
      (footprint "0603")
      (description "YAGEO 0603 0 ohm")
      (fields
        (field (name "MOUSER PART NUMBER") "603-RC0603JR-070RL")
        (field (name "MANUFACTURER_PART_NUMBER") "RC0603JR-070RL")
      )
      (libsource (lib "Resistors") (part "RC0603JR-070RL"))
    )
    (comp (ref "R96")
      (value "0R")
      (footprint "0603")
      (description "YAGEO 0603 0 ohm")
      (fields
        (field (name "MOUSER PART NUMBER") "603-RC0603JR-070RL")
        (field (name "MANUFACTURER_PART_NUMBER") "RC0603JR-070RL")
      )
      (libsource (lib "Resistors") (part "RC0603JR-070RL"))
    )
    (comp (ref "R97")
      (value "0R")
      (footprint "0603")
      (description "YAGEO 0603 0 ohm")
      (fields
        (field (name "MOUSER PART NUMBER") "603-RC0603JR-070RL")
        (field (name "MANUFACTURER_PART_NUMBER") "RC0603JR-070RL")
      )
      (libsource (lib "Resistors") (part "RC0603JR-070RL"))
    )
    (comp (ref "R98")
      (value "0R")
      (footprint "0603")
      (description "YAGEO 0603 0 ohm")
      (fields
        (field (name "MOUSER PART NUMBER") "603-RC0603JR-070RL")
        (field (name "MANUFACTURER_PART_NUMBER") "RC0603JR-070RL")
      )
      (libsource (lib "Resistors") (part "RC0603JR-070RL"))
    )
    (comp (ref "R99")
      (value "0R")
      (footprint "0603")
      (description "YAGEO 0603 0 ohm")
      (fields
        (field (name "MOUSER PART NUMBER") "603-RC0603JR-070RL")
        (field (name "MANUFACTURER_PART_NUMBER") "RC0603JR-070RL")
      )
      (libsource (lib "Resistors") (part "RC0603JR-070RL"))
    )
    (comp (ref "R100")
      (value "0R")
      (footprint "0603")
      (description "YAGEO 0603 0 ohm")
      (fields
        (field (name "MOUSER PART NUMBER") "603-RC0603JR-070RL")
        (field (name "MANUFACTURER_PART_NUMBER") "RC0603JR-070RL")
      )
      (libsource (lib "Resistors") (part "RC0603JR-070RL"))
    )
    (comp (ref "R101")
      (value "0R")
      (footprint "0603")
      (description "YAGEO 0603 0 ohm")
      (fields
        (field (name "MOUSER PART NUMBER") "603-RC0603JR-070RL")
        (field (name "MANUFACTURER_PART_NUMBER") "RC0603JR-070RL")
      )
      (libsource (lib "Resistors") (part "RC0603JR-070RL"))
    )
    (comp (ref "R102")
      (value "0R")
      (footprint "0603")
      (description "YAGEO 0603 0 ohm")
      (fields
        (field (name "MOUSER PART NUMBER") "603-RC0603JR-070RL")
        (field (name "MANUFACTURER_PART_NUMBER") "RC0603JR-070RL")
      )
      (libsource (lib "Resistors") (part "RC0603JR-070RL"))
    )
    (comp (ref "R103")
      (value "0R")
      (footprint "0603")
      (description "YAGEO 0603 0 ohm")
      (fields
        (field (name "MOUSER PART NUMBER") "603-RC0603JR-070RL")
        (field (name "MANUFACTURER_PART_NUMBER") "RC0603JR-070RL")
      )
      (libsource (lib "Resistors") (part "RC0603JR-070RL"))
    )
    (comp (ref "R104")
      (value "0R")
      (footprint "0603")
      (description "YAGEO 0603 0 ohm")
      (fields
        (field (name "MOUSER PART NUMBER") "603-RC0603JR-070RL")
        (field (name "MANUFACTURER_PART_NUMBER") "RC0603JR-070RL")
      )
      (libsource (lib "Resistors") (part "RC0603JR-070RL"))
    )
    (comp (ref "R105")
      (value "0R")
      (footprint "0603")
      (description "YAGEO 0603 0 ohm")
      (fields
        (field (name "MOUSER PART NUMBER") "603-RC0603JR-070RL")
        (field (name "MANUFACTURER_PART_NUMBER") "RC0603JR-070RL")
      )
      (libsource (lib "Resistors") (part "RC0603JR-070RL"))
    )
    (comp (ref "R106")
      (value "0R")
      (footprint "0603")
      (description "YAGEO 0603 0 ohm")
      (fields
        (field (name "MOUSER PART NUMBER") "603-RC0603JR-070RL")
        (field (name "MANUFACTURER_PART_NUMBER") "RC0603JR-070RL")
      )
      (libsource (lib "Resistors") (part "RC0603JR-070RL"))
    )
    (comp (ref "R107")
      (value "0R")
      (footprint "0603")
      (description "YAGEO 0603 0 ohm")
      (fields
        (field (name "MOUSER PART NUMBER") "603-RC0603JR-070RL")
        (field (name "MANUFACTURER_PART_NUMBER") "RC0603JR-070RL")
      )
      (libsource (lib "Resistors") (part "RC0603JR-070RL"))
    )
    (comp (ref "R108")
      (value "0R")
      (footprint "0603")
      (description "YAGEO 0603 0 ohm")
      (fields
        (field (name "MOUSER PART NUMBER") "603-RC0603JR-070RL")
        (field (name "MANUFACTURER_PART_NUMBER") "RC0603JR-070RL")
      )
      (libsource (lib "Resistors") (part "RC0603JR-070RL"))
    )
    (comp (ref "R109")
      (value "0R")
      (footprint "0603")
      (description "YAGEO 0603 0 ohm")
      (fields
        (field (name "MOUSER PART NUMBER") "603-RC0603JR-070RL")
        (field (name "MANUFACTURER_PART_NUMBER") "RC0603JR-070RL")
      )
      (libsource (lib "Resistors") (part "RC0603JR-070RL"))
    )
    (comp (ref "R110")
      (value "0R")
      (footprint "0603")
      (description "YAGEO 0603 0 ohm")
      (fields
        (field (name "MOUSER PART NUMBER") "603-RC0603JR-070RL")
        (field (name "MANUFACTURER_PART_NUMBER") "RC0603JR-070RL")
      )
      (libsource (lib "Resistors") (part "RC0603JR-070RL"))
    )
    (comp (ref "R111")
      (value "0R")
      (footprint "0603")
      (description "YAGEO 0603 0 ohm")
      (fields
        (field (name "MOUSER PART NUMBER") "603-RC0603JR-070RL")
        (field (name "MANUFACTURER_PART_NUMBER") "RC0603JR-070RL")
      )
      (libsource (lib "Resistors") (part "RC0603JR-070RL"))
    )
    (comp (ref "R112")
      (value "0R")
      (footprint "0603")
      (description "YAGEO 0603 0 ohm")
      (fields
        (field (name "MOUSER PART NUMBER") "603-RC0603JR-070RL")
        (field (name "MANUFACTURER_PART_NUMBER") "RC0603JR-070RL")
      )
      (libsource (lib "Resistors") (part "RC0603JR-070RL"))
    )
    (comp (ref "R113")
      (value "0R")
      (footprint "0603")
      (description "YAGEO 0603 0 ohm")
      (fields
        (field (name "MOUSER PART NUMBER") "603-RC0603JR-070RL")
        (field (name "MANUFACTURER_PART_NUMBER") "RC0603JR-070RL")
      )
      (libsource (lib "Resistors") (part "RC0603JR-070RL"))
    )
    (comp (ref "R114")
      (value "0R")
      (footprint "0603")
      (description "YAGEO 0603 0 ohm")
      (fields
        (field (name "MOUSER PART NUMBER") "603-RC0603JR-070RL")
        (field (name "MANUFACTURER_PART_NUMBER") "RC0603JR-070RL")
      )
      (libsource (lib "Resistors") (part "RC0603JR-070RL"))
    )
    (comp (ref "R115")
      (value "0R")
      (footprint "0603")
      (description "YAGEO 0603 0 ohm")
      (fields
        (field (name "MOUSER PART NUMBER") "603-RC0603JR-070RL")
        (field (name "MANUFACTURER_PART_NUMBER") "RC0603JR-070RL")
      )
      (libsource (lib "Resistors") (part "RC0603JR-070RL"))
    )
    (comp (ref "TitleBlock_1") (value "TitleBlock") (libsource (lib "Misc") (part "TitleBlock")))
    (comp (ref "TP1")
      (value "TP")
      (footprint "TP")
      (fields
        (field (name "MANUFACTURER") "Samtec")
        (field (name "MANUFACTURER PART NUMBER") "TST-105-01-G-D")
      )
      (libsource (lib "Misc") (part "TP"))
    )
    (comp (ref "TP2")
      (value "TP")
      (footprint "TP")
      (fields
        (field (name "MANUFACTURER") "Samtec")
        (field (name "MANUFACTURER PART NUMBER") "TST-105-01-G-D")
      )
      (libsource (lib "") (part "TP_2"))
    )
    (comp (ref "TP3")
      (value "TP")
      (footprint "TP")
      (fields
        (field (name "MANUFACTURER") "Samtec")
        (field (name "MANUFACTURER PART NUMBER") "TST-105-01-G-D")
      )
      (libsource (lib "") (part "TP_1"))
    )
    (comp (ref "TP4")
      (value "TP")
      (footprint "TP")
      (fields
        (field (name "MANUFACTURER") "Samtec")
        (field (name "MANUFACTURER PART NUMBER") "TST-105-01-G-D")
      )
      (libsource (lib "") (part "TP_2"))
    )
    (comp (ref "TP5")
      (value "TP")
      (footprint "TP")
      (fields
        (field (name "MANUFACTURER") "Samtec")
        (field (name "MANUFACTURER PART NUMBER") "TST-105-01-G-D")
      )
      (libsource (lib "Misc") (part "TP"))
    )
    (comp (ref "TP6")
      (value "TP")
      (footprint "TP")
      (fields
        (field (name "MANUFACTURER") "Samtec")
        (field (name "MANUFACTURER PART NUMBER") "TST-105-01-G-D")
      )
      (libsource (lib "") (part "TP_2"))
    )
    (comp (ref "TP7")
      (value "TP")
      (footprint "TP")
      (fields
        (field (name "MANUFACTURER") "Samtec")
        (field (name "MANUFACTURER PART NUMBER") "TST-105-01-G-D")
      )
      (libsource (lib "") (part "TP_2"))
    )
  )
  (nets
    (net (code "1") (name "+3.3") (class "Default")
      (node (ref "H1") (pin "3") (pinfunction "3_3") (pintype "passive"))
      (node (ref "TP1") (pin "1") (pinfunction "1_1") (pintype "passive"))
    )
    (net (code "2") (name "+5") (class "Default")
      (node (ref "B1") (pin "16") (pinfunction "VCC_16") (pintype "passive"))
      (node (ref "B2") (pin "16") (pinfunction "VCC_16") (pintype "passive"))
      (node (ref "B3") (pin "16") (pinfunction "VCC_16") (pintype "passive"))
      (node (ref "C1") (pin "1") (pinfunction "1_1") (pintype "passive"))
      (node (ref "C2") (pin "1") (pinfunction "1_1") (pintype "passive"))
      (node (ref "C3") (pin "1") (pinfunction "1_1") (pintype "passive"))
      (node (ref "C4") (pin "1") (pinfunction "1_1") (pintype "passive"))
      (node (ref "C5") (pin "1") (pinfunction "1_1") (pintype "passive"))
      (node (ref "C6") (pin "1") (pinfunction "1_1") (pintype "passive"))
      (node (ref "H1") (pin "1") (pinfunction "1_1") (pintype "passive"))
      (node (ref "H2") (pin "2") (pinfunction "VDD_2") (pintype "passive"))
      (node (ref "H3") (pin "1") (pinfunction "1_1") (pintype "passive"))
      (node (ref "H4") (pin "1") (pinfunction "1_1") (pintype "passive"))
      (node (ref "H5") (pin "1") (pinfunction "1_1") (pintype "passive"))
      (node (ref "H6") (pin "1") (pinfunction "1_1") (pintype "passive"))
      (node (ref "H7") (pin "1") (pinfunction "1_1") (pintype "passive"))
      (node (ref "IC1") (pin "10") (pinfunction "VDDIO2_10") (pintype "passive"))
      (node (ref "IC1") (pin "18") (pinfunction "VDD_1_18") (pintype "passive"))
      (node (ref "IC1") (pin "28") (pinfunction "VDD_2_28") (pintype "passive"))
      (node (ref "R23") (pin "2") (pinfunction "2_2") (pintype "passive"))
      (node (ref "R24") (pin "2") (pinfunction "2_2") (pintype "passive"))
    )
    (net (code "3") (name "/CPU_CS") (class "Default")
      (node (ref "R12") (pin "2") (pinfunction "2_2") (pintype "passive"))
      (node (ref "R43") (pin "2") (pinfunction "2_2") (pintype "passive"))
    )
    (net (code "4") (name "/CPU_D0") (class "Default")
      (node (ref "R1") (pin "1") (pinfunction "1_1") (pintype "passive"))
      (node (ref "R17") (pin "1") (pinfunction "1_1") (pintype "passive"))
    )
    (net (code "5") (name "/CPU_D1") (class "Default")
      (node (ref "R19") (pin "1") (pinfunction "1_1") (pintype "passive"))
      (node (ref "R3") (pin "1") (pinfunction "1_1") (pintype "passive"))
    )
    (net (code "6") (name "/CPU_D2") (class "Default")
      (node (ref "R21") (pin "1") (pinfunction "1_1") (pintype "passive"))
      (node (ref "R6") (pin "1") (pinfunction "1_1") (pintype "passive"))
    )
    (net (code "7") (name "/CPU_D3") (class "Default")
      (node (ref "R25") (pin "1") (pinfunction "1_1") (pintype "passive"))
      (node (ref "R9") (pin "1") (pinfunction "1_1") (pintype "passive"))
    )
    (net (code "8") (name "/CPU_D4") (class "Default")
      (node (ref "R11") (pin "1") (pinfunction "1_1") (pintype "passive"))
      (node (ref "R27") (pin "1") (pinfunction "1_1") (pintype "passive"))
    )
    (net (code "9") (name "/CPU_D5") (class "Default")
      (node (ref "R13") (pin "1") (pinfunction "1_1") (pintype "passive"))
      (node (ref "R29") (pin "1") (pinfunction "1_1") (pintype "passive"))
    )
    (net (code "10") (name "/CPU_D6") (class "Default")
      (node (ref "R15") (pin "1") (pinfunction "1_1") (pintype "passive"))
      (node (ref "R31") (pin "1") (pinfunction "1_1") (pintype "passive"))
    )
    (net (code "11") (name "/CPU_D7") (class "Default")
      (node (ref "R16") (pin "1") (pinfunction "1_1") (pintype "passive"))
      (node (ref "R33") (pin "1") (pinfunction "1_1") (pintype "passive"))
    )
    (net (code "12") (name "/CPU_Reset") (class "Default")
      (node (ref "R14") (pin "2") (pinfunction "2_2") (pintype "passive"))
      (node (ref "R20") (pin "2") (pinfunction "2_2") (pintype "passive"))
    )
    (net (code "13") (name "/CPU_RnW") (class "Default")
      (node (ref "R10") (pin "2") (pinfunction "2_2") (pintype "passive"))
      (node (ref "R44") (pin "2") (pinfunction "2_2") (pintype "passive"))
    )
    (net (code "14") (name "/CPU_nInt") (class "Default")
      (node (ref "R45") (pin "2") (pinfunction "2_2") (pintype "passive"))
      (node (ref "R7") (pin "2") (pinfunction "2_2") (pintype "passive"))
    )
    (net (code "15") (name "/I2C_SDA") (class "Default")
      (node (ref "J2") (pin "2") (pinfunction "2_2") (pintype "passive"))
      (node (ref "R40") (pin "1") (pinfunction "1_1") (pintype "passive"))
      (node (ref "R46") (pin "1") (pinfunction "1_1") (pintype "passive"))
    )
    (net (code "16") (name "/I2C_SDC") (class "Default")
      (node (ref "J1") (pin "2") (pinfunction "2_2") (pintype "passive"))
      (node (ref "R42") (pin "1") (pinfunction "1_1") (pintype "passive"))
      (node (ref "R47") (pin "1") (pinfunction "1_1") (pintype "passive"))
    )
    (net (code "17") (name "/LCD1_CnD") (class "Default")
      (node (ref "R52") (pin "1") (pinfunction "1_1") (pintype "passive"))
      (node (ref "R53") (pin "2") (pinfunction "2_2") (pintype "passive"))
    )
    (net (code "18") (name "/LCD1_Extra") (class "Default")
      (node (ref "R77") (pin "1") (pinfunction "1_1") (pintype "passive"))
      (node (ref "R79") (pin "2") (pinfunction "2_2") (pintype "passive"))
    )
    (net (code "19") (name "/LCD1_FS") (class "Default")
      (node (ref "R74") (pin "1") (pinfunction "1_1") (pintype "passive"))
      (node (ref "R76") (pin "2") (pinfunction "2_2") (pintype "passive"))
    )
    (net (code "20") (name "/LCD1_Mid") (class "Default")
      (node (ref "R70") (pin "1") (pinfunction "1_1") (pintype "passive"))
      (node (ref "R73") (pin "2") (pinfunction "2_2") (pintype "passive"))
    )
    (net (code "21") (name "/LCD1_Reset") (class "Default")
      (node (ref "R62") (pin "1") (pinfunction "1_1") (pintype "passive"))
      (node (ref "R65") (pin "2") (pinfunction "2_2") (pintype "passive"))
    )
    (net (code "22") (name "/LCD1_nCE") (class "Default")
      (node (ref "R66") (pin "1") (pinfunction "1_1") (pintype "passive"))
      (node (ref "R69") (pin "2") (pinfunction "2_2") (pintype "passive"))
    )
    (net (code "23") (name "/LCD1_nRD") (class "Default")
      (node (ref "R54") (pin "1") (pinfunction "1_1") (pintype "passive"))
      (node (ref "R57") (pin "2") (pinfunction "2_2") (pintype "passive"))
    )
    (net (code "24") (name "/LCD1_nWR") (class "Default")
      (node (ref "R58") (pin "1") (pinfunction "1_1") (pintype "passive"))
      (node (ref "R61") (pin "2") (pinfunction "2_2") (pintype "passive"))
    )
    (net (code "25") (name "/LCD2_DnI") (class "Default")
      (node (ref "R111") (pin "2") (pinfunction "2_2") (pintype "passive"))
      (node (ref "R92") (pin "1") (pinfunction "1_1") (pintype "passive"))
    )
    (net (code "26") (name "/LCD2_Enable") (class "Default")
      (node (ref "R113") (pin "2") (pinfunction "2_2") (pintype "passive"))
      (node (ref "R95") (pin "1") (pinfunction "1_1") (pintype "passive"))
    )
    (net (code "27") (name "/LCD2_Extra_1") (class "Default")
      (node (ref "R114") (pin "2") (pinfunction "2_2") (pintype "passive"))
      (node (ref "R98") (pin "1") (pinfunction "1_1") (pintype "passive"))
    )
    (net (code "28") (name "/LCD2_Extra_2") (class "Default")
      (node (ref "R101") (pin "1") (pinfunction "1_1") (pintype "passive"))
      (node (ref "R115") (pin "2") (pinfunction "2_2") (pintype "passive"))
    )
    (net (code "29") (name "/LCD2_Reset") (class "Default")
      (node (ref "R106") (pin "2") (pinfunction "2_2") (pintype "passive"))
      (node (ref "R86") (pin "1") (pinfunction "1_1") (pintype "passive"))
    )
    (net (code "30") (name "/LCD2_RnW") (class "Default")
      (node (ref "R109") (pin "2") (pinfunction "2_2") (pintype "passive"))
      (node (ref "R89") (pin "1") (pinfunction "1_1") (pintype "passive"))
    )
    (net (code "31") (name "/LCD2_nCS1") (class "Default")
      (node (ref "R100") (pin "2") (pinfunction "2_2") (pintype "passive"))
      (node (ref "R81") (pin "1") (pinfunction "1_1") (pintype "passive"))
    )
    (net (code "32") (name "/LCD2_nCS2") (class "Default")
      (node (ref "R104") (pin "2") (pinfunction "2_2") (pintype "passive"))
      (node (ref "R83") (pin "1") (pinfunction "1_1") (pintype "passive"))
    )
    (net (code "33") (name "/LCD_D0") (class "Default")
      (node (ref "H4") (pin "2") (pinfunction "2_2") (pintype "passive"))
      (node (ref "H7") (pin "2") (pinfunction "2_2") (pintype "passive"))
      (node (ref "R82") (pin "2") (pinfunction "2_2") (pintype "passive"))
    )
    (net (code "34") (name "/LCD_D1") (class "Default")
      (node (ref "H4") (pin "3") (pinfunction "3_3") (pintype "passive"))
      (node (ref "H7") (pin "3") (pinfunction "3_3") (pintype "passive"))
      (node (ref "R85") (pin "2") (pinfunction "2_2") (pintype "passive"))
    )
    (net (code "35") (name "/LCD_D2") (class "Default")
      (node (ref "H4") (pin "4") (pinfunction "4_4") (pintype "passive"))
      (node (ref "H7") (pin "4") (pinfunction "4_4") (pintype "passive"))
      (node (ref "R88") (pin "2") (pinfunction "2_2") (pintype "passive"))
    )
    (net (code "36") (name "/LCD_D3") (class "Default")
      (node (ref "H4") (pin "5") (pinfunction "5_5") (pintype "passive"))
      (node (ref "H7") (pin "5") (pinfunction "5_5") (pintype "passive"))
      (node (ref "R91") (pin "2") (pinfunction "2_2") (pintype "passive"))
    )
    (net (code "37") (name "/LCD_D4") (class "Default")
      (node (ref "H4") (pin "6") (pinfunction "6_6") (pintype "passive"))
      (node (ref "H7") (pin "6") (pinfunction "6_6") (pintype "passive"))
      (node (ref "R94") (pin "2") (pinfunction "2_2") (pintype "passive"))
    )
    (net (code "38") (name "/LCD_D5") (class "Default")
      (node (ref "H4") (pin "7") (pinfunction "7_7") (pintype "passive"))
      (node (ref "H7") (pin "7") (pinfunction "7_7") (pintype "passive"))
      (node (ref "R97") (pin "2") (pinfunction "2_2") (pintype "passive"))
    )
    (net (code "39") (name "/LCD_D6") (class "Default")
      (node (ref "H4") (pin "8") (pinfunction "8_8") (pintype "passive"))
      (node (ref "H7") (pin "8") (pinfunction "8_8") (pintype "passive"))
      (node (ref "R99") (pin "2") (pinfunction "2_2") (pintype "passive"))
    )
    (net (code "40") (name "/LCD_D7") (class "Default")
      (node (ref "H4") (pin "9") (pinfunction "9_9") (pintype "passive"))
      (node (ref "H7") (pin "9") (pinfunction "9_9") (pintype "passive"))
      (node (ref "R102") (pin "2") (pinfunction "2_2") (pintype "passive"))
    )
    (net (code "41") (name "/RCLK") (class "Default")
      (node (ref "R108") (pin "1") (pinfunction "1_1") (pintype "passive"))
      (node (ref "R28") (pin "2") (pinfunction "2_2") (pintype "passive"))
      (node (ref "R64") (pin "1") (pinfunction "1_1") (pintype "passive"))
      (node (ref "R90") (pin "1") (pinfunction "1_1") (pintype "passive"))
    )
    (net (code "42") (name "/SCLK") (class "Default")
      (node (ref "R110") (pin "1") (pinfunction "1_1") (pintype "passive"))
      (node (ref "R30") (pin "2") (pinfunction "2_2") (pintype "passive"))
      (node (ref "R68") (pin "1") (pinfunction "1_1") (pintype "passive"))
      (node (ref "R93") (pin "1") (pinfunction "1_1") (pintype "passive"))
    )
    (net (code "43") (name "/SCLR") (class "Default")
      (node (ref "R112") (pin "1") (pinfunction "1_1") (pintype "passive"))
      (node (ref "R32") (pin "2") (pinfunction "2_2") (pintype "passive"))
      (node (ref "R72") (pin "1") (pinfunction "1_1") (pintype "passive"))
      (node (ref "R96") (pin "1") (pinfunction "1_1") (pintype "passive"))
    )
    (net (code "44") (name "/SER_Data_0") (class "Default")
      (node (ref "R22") (pin "2") (pinfunction "2_2") (pintype "passive"))
      (node (ref "R84") (pin "1") (pinfunction "1_1") (pintype "passive"))
    )
    (net (code "45") (name "/SER_Data_1") (class "Default")
      (node (ref "R107") (pin "2") (pinfunction "2_2") (pintype "passive"))
      (node (ref "R56") (pin "1") (pinfunction "1_1") (pintype "passive"))
    )
    (net (code "46") (name "/SER_Data_2") (class "Default")
      (node (ref "R103") (pin "1") (pinfunction "1_1") (pintype "passive"))
      (node (ref "R80") (pin "2") (pinfunction "2_2") (pintype "passive"))
    )
    (net (code "47") (name "/SPI_MISO") (class "Default")
      (node (ref "R39") (pin "2") (pinfunction "2_2") (pintype "passive"))
      (node (ref "R50") (pin "1") (pinfunction "1_1") (pintype "passive"))
    )
    (net (code "48") (name "/SPI_MOSI") (class "Default")
      (node (ref "R41") (pin "2") (pinfunction "2_2") (pintype "passive"))
      (node (ref "R51") (pin "1") (pinfunction "1_1") (pintype "passive"))
    )
    (net (code "49") (name "/SPI_SCK") (class "Default")
      (node (ref "R37") (pin "2") (pinfunction "2_2") (pintype "passive"))
      (node (ref "R49") (pin "1") (pinfunction "1_1") (pintype "passive"))
    )
    (net (code "50") (name "/SPI_SS") (class "Default")
      (node (ref "R35") (pin "2") (pinfunction "2_2") (pintype "passive"))
      (node (ref "R48") (pin "1") (pinfunction "1_1") (pintype "passive"))
    )
    (net (code "51") (name "/UPDI") (class "Default")
      (node (ref "R18") (pin "2") (pinfunction "2_2") (pintype "passive"))
      (node (ref "R2") (pin "1") (pinfunction "1_1") (pintype "passive"))
    )
    (net (code "52") (name "/nOE") (class "Default")
      (node (ref "R105") (pin "1") (pinfunction "1_1") (pintype "passive"))
      (node (ref "R26") (pin "2") (pinfunction "2_2") (pintype "passive"))
      (node (ref "R60") (pin "1") (pinfunction "1_1") (pintype "passive"))
      (node (ref "R87") (pin "1") (pinfunction "1_1") (pintype "passive"))
    )
    (net (code "53") (name "GND") (class "Default")
      (node (ref "B1") (pin "8") (pinfunction "GND_8") (pintype "passive"))
      (node (ref "B2") (pin "8") (pinfunction "GND_8") (pintype "passive"))
      (node (ref "B3") (pin "8") (pinfunction "GND_8") (pintype "passive"))
      (node (ref "C1") (pin "2") (pinfunction "2_2") (pintype "passive"))
      (node (ref "C2") (pin "2") (pinfunction "2_2") (pintype "passive"))
      (node (ref "C3") (pin "2") (pinfunction "2_2") (pintype "passive"))
      (node (ref "C4") (pin "2") (pinfunction "2_2") (pintype "passive"))
      (node (ref "C5") (pin "2") (pinfunction "2_2") (pintype "passive"))
      (node (ref "C6") (pin "2") (pinfunction "2_2") (pintype "passive"))
      (node (ref "H1") (pin "13") (pinfunction "13_13") (pintype "passive"))
      (node (ref "H1") (pin "15") (pinfunction "15_15") (pintype "passive"))
      (node (ref "H2") (pin "6") (pinfunction "GND_6") (pintype "passive"))
      (node (ref "H3") (pin "10") (pinfunction "10_10") (pintype "passive"))
      (node (ref "H3") (pin "9") (pinfunction "9_9") (pintype "passive"))
      (node (ref "H4") (pin "10") (pinfunction "10_10") (pintype "passive"))
      (node (ref "H5") (pin "10") (pinfunction "10_10") (pintype "passive"))
      (node (ref "H6") (pin "10") (pinfunction "10_10") (pintype "passive"))
      (node (ref "H7") (pin "10") (pinfunction "10_10") (pintype "passive"))
      (node (ref "IC1") (pin "19") (pinfunction "GND_1_19") (pintype "passive"))
      (node (ref "IC1") (pin "29") (pinfunction "GND_2_29") (pintype "passive"))
    )
    (net (code "54") (name "Net-(B1-QA)") (class "Default")
      (node (ref "B1") (pin "15") (pinfunction "QA_15") (pintype "passive"))
      (node (ref "R53") (pin "1") (pinfunction "1_1") (pintype "passive"))
    )
    (net (code "55") (name "Net-(B1-QB)") (class "Default")
      (node (ref "B1") (pin "1") (pinfunction "QB_1") (pintype "passive"))
      (node (ref "R57") (pin "1") (pinfunction "1_1") (pintype "passive"))
    )
    (net (code "56") (name "Net-(B1-QC)") (class "Default")
      (node (ref "B1") (pin "2") (pinfunction "QC_2") (pintype "passive"))
      (node (ref "R61") (pin "1") (pinfunction "1_1") (pintype "passive"))
    )
    (net (code "57") (name "Net-(B1-QD)") (class "Default")
      (node (ref "B1") (pin "3") (pinfunction "QD_3") (pintype "passive"))
      (node (ref "R65") (pin "1") (pinfunction "1_1") (pintype "passive"))
    )
    (net (code "58") (name "Net-(B1-QE)") (class "Default")
      (node (ref "B1") (pin "4") (pinfunction "QE_4") (pintype "passive"))
      (node (ref "R69") (pin "1") (pinfunction "1_1") (pintype "passive"))
    )
    (net (code "59") (name "Net-(B1-QF)") (class "Default")
      (node (ref "B1") (pin "5") (pinfunction "QF_5") (pintype "passive"))
      (node (ref "R73") (pin "1") (pinfunction "1_1") (pintype "passive"))
    )
    (net (code "60") (name "Net-(B1-QG)") (class "Default")
      (node (ref "B1") (pin "6") (pinfunction "QG_6") (pintype "passive"))
      (node (ref "R76") (pin "1") (pinfunction "1_1") (pintype "passive"))
    )
    (net (code "61") (name "Net-(B1-QH)") (class "Default")
      (node (ref "B1") (pin "7") (pinfunction "QH_7") (pintype "passive"))
      (node (ref "R79") (pin "1") (pinfunction "1_1") (pintype "passive"))
    )
    (net (code "62") (name "Net-(B1-RCK)") (class "Default")
      (node (ref "B1") (pin "12") (pinfunction "RCK_12") (pintype "passive"))
      (node (ref "R64") (pin "2") (pinfunction "2_2") (pintype "passive"))
    )
    (net (code "63") (name "Net-(B1-SCK)") (class "Default")
      (node (ref "B1") (pin "11") (pinfunction "SCK_11") (pintype "passive"))
      (node (ref "R68") (pin "2") (pinfunction "2_2") (pintype "passive"))
    )
    (net (code "64") (name "Net-(B1-SER)") (class "Default")
      (node (ref "B1") (pin "14") (pinfunction "SER_14") (pintype "passive"))
      (node (ref "R56") (pin "2") (pinfunction "2_2") (pintype "passive"))
    )
    (net (code "65") (name "Net-(B1-Serial_Out)") (class "Default")
      (node (ref "B1") (pin "9") (pinfunction "Serial_Out_9") (pintype "passive"))
      (node (ref "R80") (pin "1") (pinfunction "1_1") (pintype "passive"))
    )
    (net (code "66") (name "Net-(B1-~{G})") (class "Default")
      (node (ref "B1") (pin "13") (pinfunction "~{G}_13") (pintype "passive"))
      (node (ref "R60") (pin "2") (pinfunction "2_2") (pintype "passive"))
    )
    (net (code "67") (name "Net-(B1-~{SCLR})") (class "Default")
      (node (ref "B1") (pin "10") (pinfunction "~{SCLR}_10") (pintype "passive"))
      (node (ref "R72") (pin "2") (pinfunction "2_2") (pintype "passive"))
    )
    (net (code "68") (name "Net-(B2-QA)") (class "Default")
      (node (ref "B2") (pin "15") (pinfunction "QA_15") (pintype "passive"))
      (node (ref "R82") (pin "1") (pinfunction "1_1") (pintype "passive"))
    )
    (net (code "69") (name "Net-(B2-QB)") (class "Default")
      (node (ref "B2") (pin "1") (pinfunction "QB_1") (pintype "passive"))
      (node (ref "R85") (pin "1") (pinfunction "1_1") (pintype "passive"))
    )
    (net (code "70") (name "Net-(B2-QC)") (class "Default")
      (node (ref "B2") (pin "2") (pinfunction "QC_2") (pintype "passive"))
      (node (ref "R88") (pin "1") (pinfunction "1_1") (pintype "passive"))
    )
    (net (code "71") (name "Net-(B2-QD)") (class "Default")
      (node (ref "B2") (pin "3") (pinfunction "QD_3") (pintype "passive"))
      (node (ref "R91") (pin "1") (pinfunction "1_1") (pintype "passive"))
    )
    (net (code "72") (name "Net-(B2-QE)") (class "Default")
      (node (ref "B2") (pin "4") (pinfunction "QE_4") (pintype "passive"))
      (node (ref "R94") (pin "1") (pinfunction "1_1") (pintype "passive"))
    )
    (net (code "73") (name "Net-(B2-QF)") (class "Default")
      (node (ref "B2") (pin "5") (pinfunction "QF_5") (pintype "passive"))
      (node (ref "R97") (pin "1") (pinfunction "1_1") (pintype "passive"))
    )
    (net (code "74") (name "Net-(B2-QG)") (class "Default")
      (node (ref "B2") (pin "6") (pinfunction "QG_6") (pintype "passive"))
      (node (ref "R99") (pin "1") (pinfunction "1_1") (pintype "passive"))
    )
    (net (code "75") (name "Net-(B2-QH)") (class "Default")
      (node (ref "B2") (pin "7") (pinfunction "QH_7") (pintype "passive"))
      (node (ref "R102") (pin "1") (pinfunction "1_1") (pintype "passive"))
    )
    (net (code "76") (name "Net-(B2-RCK)") (class "Default")
      (node (ref "B2") (pin "12") (pinfunction "RCK_12") (pintype "passive"))
      (node (ref "R90") (pin "2") (pinfunction "2_2") (pintype "passive"))
    )
    (net (code "77") (name "Net-(B2-SCK)") (class "Default")
      (node (ref "B2") (pin "11") (pinfunction "SCK_11") (pintype "passive"))
      (node (ref "R93") (pin "2") (pinfunction "2_2") (pintype "passive"))
    )
    (net (code "78") (name "Net-(B2-SER)") (class "Default")
      (node (ref "B2") (pin "14") (pinfunction "SER_14") (pintype "passive"))
      (node (ref "R84") (pin "2") (pinfunction "2_2") (pintype "passive"))
    )
    (net (code "79") (name "Net-(B2-Serial_Out)") (class "Default")
      (node (ref "B2") (pin "9") (pinfunction "Serial_Out_9") (pintype "passive"))
      (node (ref "R107") (pin "1") (pinfunction "1_1") (pintype "passive"))
    )
    (net (code "80") (name "Net-(B2-~{G})") (class "Default")
      (node (ref "B2") (pin "13") (pinfunction "~{G}_13") (pintype "passive"))
      (node (ref "R87") (pin "2") (pinfunction "2_2") (pintype "passive"))
    )
    (net (code "81") (name "Net-(B2-~{SCLR})") (class "Default")
      (node (ref "B2") (pin "10") (pinfunction "~{SCLR}_10") (pintype "passive"))
      (node (ref "R96") (pin "2") (pinfunction "2_2") (pintype "passive"))
    )
    (net (code "82") (name "Net-(B3-QA)") (class "Default")
      (node (ref "B3") (pin "15") (pinfunction "QA_15") (pintype "passive"))
      (node (ref "R100") (pin "1") (pinfunction "1_1") (pintype "passive"))
    )
    (net (code "83") (name "Net-(B3-QB)") (class "Default")
      (node (ref "B3") (pin "1") (pinfunction "QB_1") (pintype "passive"))
      (node (ref "R104") (pin "1") (pinfunction "1_1") (pintype "passive"))
    )
    (net (code "84") (name "Net-(B3-QC)") (class "Default")
      (node (ref "B3") (pin "2") (pinfunction "QC_2") (pintype "passive"))
      (node (ref "R106") (pin "1") (pinfunction "1_1") (pintype "passive"))
    )
    (net (code "85") (name "Net-(B3-QD)") (class "Default")
      (node (ref "B3") (pin "3") (pinfunction "QD_3") (pintype "passive"))
      (node (ref "R109") (pin "1") (pinfunction "1_1") (pintype "passive"))
    )
    (net (code "86") (name "Net-(B3-QE)") (class "Default")
      (node (ref "B3") (pin "4") (pinfunction "QE_4") (pintype "passive"))
      (node (ref "R111") (pin "1") (pinfunction "1_1") (pintype "passive"))
    )
    (net (code "87") (name "Net-(B3-QF)") (class "Default")
      (node (ref "B3") (pin "5") (pinfunction "QF_5") (pintype "passive"))
      (node (ref "R113") (pin "1") (pinfunction "1_1") (pintype "passive"))
    )
    (net (code "88") (name "Net-(B3-QG)") (class "Default")
      (node (ref "B3") (pin "6") (pinfunction "QG_6") (pintype "passive"))
      (node (ref "R114") (pin "1") (pinfunction "1_1") (pintype "passive"))
    )
    (net (code "89") (name "Net-(B3-QH)") (class "Default")
      (node (ref "B3") (pin "7") (pinfunction "QH_7") (pintype "passive"))
      (node (ref "R115") (pin "1") (pinfunction "1_1") (pintype "passive"))
    )
    (net (code "90") (name "Net-(B3-RCK)") (class "Default")
      (node (ref "B3") (pin "12") (pinfunction "RCK_12") (pintype "passive"))
      (node (ref "R108") (pin "2") (pinfunction "2_2") (pintype "passive"))
    )
    (net (code "91") (name "Net-(B3-SCK)") (class "Default")
      (node (ref "B3") (pin "11") (pinfunction "SCK_11") (pintype "passive"))
      (node (ref "R110") (pin "2") (pinfunction "2_2") (pintype "passive"))
    )
    (net (code "92") (name "Net-(B3-SER)") (class "Default")
      (node (ref "B3") (pin "14") (pinfunction "SER_14") (pintype "passive"))
      (node (ref "R103") (pin "2") (pinfunction "2_2") (pintype "passive"))
    )
    (net (code "93") (name "Net-(B3-~{G})") (class "Default")
      (node (ref "B3") (pin "13") (pinfunction "~{G}_13") (pintype "passive"))
      (node (ref "R105") (pin "2") (pinfunction "2_2") (pintype "passive"))
    )
    (net (code "94") (name "Net-(B3-~{SCLR})") (class "Default")
      (node (ref "B3") (pin "10") (pinfunction "~{SCLR}_10") (pintype "passive"))
      (node (ref "R112") (pin "2") (pinfunction "2_2") (pintype "passive"))
    )
    (net (code "95") (name "Net-(H1-Pad2)") (class "Default")
      (node (ref "H1") (pin "2") (pinfunction "2_2") (pintype "passive"))
      (node (ref "R1") (pin "2") (pinfunction "2_2") (pintype "passive"))
    )
    (net (code "96") (name "Net-(H1-Pad4)") (class "Default")
      (node (ref "H1") (pin "4") (pinfunction "4_4") (pintype "passive"))
      (node (ref "R3") (pin "2") (pinfunction "2_2") (pintype "passive"))
    )
    (net (code "97") (name "Net-(H1-Pad5)") (class "Default")
      (node (ref "H1") (pin "5") (pinfunction "5_5") (pintype "passive"))
      (node (ref "R7") (pin "1") (pinfunction "1_1") (pintype "passive"))
    )
    (net (code "98") (name "Net-(H1-Pad6)") (class "Default")
      (node (ref "H1") (pin "6") (pinfunction "6_6") (pintype "passive"))
      (node (ref "R6") (pin "2") (pinfunction "2_2") (pintype "passive"))
    )
    (net (code "99") (name "Net-(H1-Pad7)") (class "Default")
      (node (ref "H1") (pin "7") (pinfunction "7_7") (pintype "passive"))
      (node (ref "R10") (pin "1") (pinfunction "1_1") (pintype "passive"))
    )
    (net (code "100") (name "Net-(H1-Pad8)") (class "Default")
      (node (ref "H1") (pin "8") (pinfunction "8_8") (pintype "passive"))
      (node (ref "R9") (pin "2") (pinfunction "2_2") (pintype "passive"))
    )
    (net (code "101") (name "Net-(H1-Pad9)") (class "Default")
      (node (ref "H1") (pin "9") (pinfunction "9_9") (pintype "passive"))
      (node (ref "R12") (pin "1") (pinfunction "1_1") (pintype "passive"))
    )
    (net (code "102") (name "Net-(H1-Pad10)") (class "Default")
      (node (ref "H1") (pin "10") (pinfunction "10_10") (pintype "passive"))
      (node (ref "R11") (pin "2") (pinfunction "2_2") (pintype "passive"))
    )
    (net (code "103") (name "Net-(H1-Pad11)") (class "Default")
      (node (ref "H1") (pin "11") (pinfunction "11_11") (pintype "passive"))
      (node (ref "R14") (pin "1") (pinfunction "1_1") (pintype "passive"))
    )
    (net (code "104") (name "Net-(H1-Pad12)") (class "Default")
      (node (ref "H1") (pin "12") (pinfunction "12_12") (pintype "passive"))
      (node (ref "R13") (pin "2") (pinfunction "2_2") (pintype "passive"))
    )
    (net (code "105") (name "Net-(H1-Pad14)") (class "Default")
      (node (ref "H1") (pin "14") (pinfunction "14_14") (pintype "passive"))
      (node (ref "R15") (pin "2") (pinfunction "2_2") (pintype "passive"))
    )
    (net (code "106") (name "Net-(H1-Pad16)") (class "Default")
      (node (ref "H1") (pin "16") (pinfunction "16_16") (pintype "passive"))
      (node (ref "R16") (pin "2") (pinfunction "2_2") (pintype "passive"))
    )
    (net (code "107") (name "Net-(H2-NC-Pad3)") (class "Default")
      (node (ref "H2") (pin "3") (pinfunction "NC_3") (pintype "passive"))
      (node (ref "R4") (pin "2") (pinfunction "2_2") (pintype "passive"))
    )
    (net (code "108") (name "Net-(H2-NC-Pad4)") (class "Default")
      (node (ref "H2") (pin "4") (pinfunction "NC_4") (pintype "passive"))
      (node (ref "R5") (pin "1") (pinfunction "1_1") (pintype "passive"))
    )
    (net (code "109") (name "Net-(H2-NC-Pad5)") (class "Default")
      (node (ref "H2") (pin "5") (pinfunction "NC_5") (pintype "passive"))
      (node (ref "R8") (pin "2") (pinfunction "2_2") (pintype "passive"))
    )
    (net (code "110") (name "Net-(H2-UDPI)") (class "Default")
      (node (ref "H2") (pin "1") (pinfunction "UDPI_1") (pintype "passive"))
      (node (ref "R2") (pin "2") (pinfunction "2_2") (pintype "passive"))
    )
    (net (code "111") (name "Net-(H3-Pad2)") (class "Default")
      (node (ref "H3") (pin "2") (pinfunction "2_2") (pintype "passive"))
      (node (ref "R46") (pin "2") (pinfunction "2_2") (pintype "passive"))
    )
    (net (code "112") (name "Net-(H3-Pad3)") (class "Default")
      (node (ref "H3") (pin "3") (pinfunction "3_3") (pintype "passive"))
      (node (ref "R47") (pin "2") (pinfunction "2_2") (pintype "passive"))
    )
    (net (code "113") (name "Net-(H3-Pad5)") (class "Default")
      (node (ref "H3") (pin "5") (pinfunction "5_5") (pintype "passive"))
      (node (ref "R48") (pin "2") (pinfunction "2_2") (pintype "passive"))
    )
    (net (code "114") (name "Net-(H3-Pad6)") (class "Default")
      (node (ref "H3") (pin "6") (pinfunction "6_6") (pintype "passive"))
      (node (ref "R49") (pin "2") (pinfunction "2_2") (pintype "passive"))
    )
    (net (code "115") (name "Net-(H3-Pad7)") (class "Default")
      (node (ref "H3") (pin "7") (pinfunction "7_7") (pintype "passive"))
      (node (ref "R50") (pin "2") (pinfunction "2_2") (pintype "passive"))
    )
    (net (code "116") (name "Net-(H3-Pad8)") (class "Default")
      (node (ref "H3") (pin "8") (pinfunction "8_8") (pintype "passive"))
      (node (ref "R51") (pin "2") (pinfunction "2_2") (pintype "passive"))
    )
    (net (code "117") (name "Net-(H5-Pad2)") (class "Default")
      (node (ref "H5") (pin "2") (pinfunction "2_2") (pintype "passive"))
      (node (ref "R52") (pin "2") (pinfunction "2_2") (pintype "passive"))
    )
    (net (code "118") (name "Net-(H5-Pad3)") (class "Default")
      (node (ref "H5") (pin "3") (pinfunction "3_3") (pintype "passive"))
      (node (ref "R54") (pin "2") (pinfunction "2_2") (pintype "passive"))
    )
    (net (code "119") (name "Net-(H5-Pad4)") (class "Default")
      (node (ref "H5") (pin "4") (pinfunction "4_4") (pintype "passive"))
      (node (ref "R58") (pin "2") (pinfunction "2_2") (pintype "passive"))
    )
    (net (code "120") (name "Net-(H5-Pad5)") (class "Default")
      (node (ref "H5") (pin "5") (pinfunction "5_5") (pintype "passive"))
      (node (ref "R62") (pin "2") (pinfunction "2_2") (pintype "passive"))
    )
    (net (code "121") (name "Net-(H5-Pad6)") (class "Default")
      (node (ref "H5") (pin "6") (pinfunction "6_6") (pintype "passive"))
      (node (ref "R66") (pin "2") (pinfunction "2_2") (pintype "passive"))
    )
    (net (code "122") (name "Net-(H5-Pad7)") (class "Default")
      (node (ref "H5") (pin "7") (pinfunction "7_7") (pintype "passive"))
      (node (ref "R70") (pin "2") (pinfunction "2_2") (pintype "passive"))
    )
    (net (code "123") (name "Net-(H5-Pad8)") (class "Default")
      (node (ref "H5") (pin "8") (pinfunction "8_8") (pintype "passive"))
      (node (ref "R74") (pin "2") (pinfunction "2_2") (pintype "passive"))
    )
    (net (code "124") (name "Net-(H5-Pad9)") (class "Default")
      (node (ref "H5") (pin "9") (pinfunction "9_9") (pintype "passive"))
      (node (ref "R77") (pin "2") (pinfunction "2_2") (pintype "passive"))
    )
    (net (code "125") (name "Net-(H6-Pad2)") (class "Default")
      (node (ref "H6") (pin "2") (pinfunction "2_2") (pintype "passive"))
      (node (ref "R81") (pin "2") (pinfunction "2_2") (pintype "passive"))
    )
    (net (code "126") (name "Net-(H6-Pad3)") (class "Default")
      (node (ref "H6") (pin "3") (pinfunction "3_3") (pintype "passive"))
      (node (ref "R83") (pin "2") (pinfunction "2_2") (pintype "passive"))
    )
    (net (code "127") (name "Net-(H6-Pad4)") (class "Default")
      (node (ref "H6") (pin "4") (pinfunction "4_4") (pintype "passive"))
      (node (ref "R86") (pin "2") (pinfunction "2_2") (pintype "passive"))
    )
    (net (code "128") (name "Net-(H6-Pad5)") (class "Default")
      (node (ref "H6") (pin "5") (pinfunction "5_5") (pintype "passive"))
      (node (ref "R89") (pin "2") (pinfunction "2_2") (pintype "passive"))
    )
    (net (code "129") (name "Net-(H6-Pad6)") (class "Default")
      (node (ref "H6") (pin "6") (pinfunction "6_6") (pintype "passive"))
      (node (ref "R92") (pin "2") (pinfunction "2_2") (pintype "passive"))
    )
    (net (code "130") (name "Net-(H6-Pad7)") (class "Default")
      (node (ref "H6") (pin "7") (pinfunction "7_7") (pintype "passive"))
      (node (ref "R95") (pin "2") (pinfunction "2_2") (pintype "passive"))
    )
    (net (code "131") (name "Net-(H6-Pad8)") (class "Default")
      (node (ref "H6") (pin "8") (pinfunction "8_8") (pintype "passive"))
      (node (ref "R98") (pin "2") (pinfunction "2_2") (pintype "passive"))
    )
    (net (code "132") (name "Net-(H6-Pad9)") (class "Default")
      (node (ref "H6") (pin "9") (pinfunction "9_9") (pintype "passive"))
      (node (ref "R101") (pin "2") (pinfunction "2_2") (pintype "passive"))
    )
    (net (code "133") (name "Net-(IC1-PA0)") (class "Default")
      (node (ref "IC1") (pin "30") (pinfunction "PA0_30") (pintype "passive"))
      (node (ref "R17") (pin "2") (pinfunction "2_2") (pintype "passive"))
    )
    (net (code "134") (name "Net-(IC1-PA1)") (class "Default")
      (node (ref "IC1") (pin "31") (pinfunction "PA1_31") (pintype "passive"))
      (node (ref "R19") (pin "2") (pinfunction "2_2") (pintype "passive"))
    )
    (net (code "135") (name "Net-(IC1-PA2)") (class "Default")
      (node (ref "IC1") (pin "32") (pinfunction "PA2_32") (pintype "passive"))
      (node (ref "R21") (pin "2") (pinfunction "2_2") (pintype "passive"))
    )
    (net (code "136") (name "Net-(IC1-PA3)") (class "Default")
      (node (ref "IC1") (pin "1") (pinfunction "PA3_1") (pintype "passive"))
      (node (ref "R25") (pin "2") (pinfunction "2_2") (pintype "passive"))
    )
    (net (code "137") (name "Net-(IC1-PA4)") (class "Default")
      (node (ref "IC1") (pin "2") (pinfunction "PA4_2") (pintype "passive"))
      (node (ref "R27") (pin "2") (pinfunction "2_2") (pintype "passive"))
    )
    (net (code "138") (name "Net-(IC1-PA5)") (class "Default")
      (node (ref "IC1") (pin "3") (pinfunction "PA5_3") (pintype "passive"))
      (node (ref "R29") (pin "2") (pinfunction "2_2") (pintype "passive"))
    )
    (net (code "139") (name "Net-(IC1-PA6)") (class "Default")
      (node (ref "IC1") (pin "4") (pinfunction "PA6_4") (pintype "passive"))
      (node (ref "R31") (pin "2") (pinfunction "2_2") (pintype "passive"))
    )
    (net (code "140") (name "Net-(IC1-PA7)") (class "Default")
      (node (ref "IC1") (pin "5") (pinfunction "PA7_5") (pintype "passive"))
      (node (ref "R33") (pin "2") (pinfunction "2_2") (pintype "passive"))
    )
    (net (code "141") (name "Net-(IC1-PC0)") (class "Default")
      (node (ref "IC1") (pin "6") (pinfunction "PC0_6") (pintype "passive"))
      (node (ref "R36") (pin "2") (pinfunction "2_2") (pintype "passive"))
    )
    (net (code "142") (name "Net-(IC1-PC1)") (class "Default")
      (node (ref "IC1") (pin "7") (pinfunction "PC1_7") (pintype "passive"))
      (node (ref "R38") (pin "2") (pinfunction "2_2") (pintype "passive"))
    )
    (net (code "143") (name "Net-(IC1-PC2)") (class "Default")
      (node (ref "IC1") (pin "8") (pinfunction "PC2_8") (pintype "passive"))
      (node (ref "R40") (pin "2") (pinfunction "2_2") (pintype "passive"))
    )
    (net (code "144") (name "Net-(IC1-PC3)") (class "Default")
      (node (ref "IC1") (pin "9") (pinfunction "PC3_9") (pintype "passive"))
      (node (ref "R42") (pin "2") (pinfunction "2_2") (pintype "passive"))
    )
    (net (code "145") (name "Net-(IC1-PD3)") (class "Default")
      (node (ref "IC1") (pin "13") (pinfunction "PD3_13") (pintype "passive"))
      (node (ref "R43") (pin "1") (pinfunction "1_1") (pintype "passive"))
    )
    (net (code "146") (name "Net-(IC1-PD4)") (class "Default")
      (node (ref "IC1") (pin "14") (pinfunction "PD4_14") (pintype "passive"))
      (node (ref "R41") (pin "1") (pinfunction "1_1") (pintype "passive"))
    )
    (net (code "147") (name "Net-(IC1-PD5)") (class "Default")
      (node (ref "IC1") (pin "15") (pinfunction "PD5_15") (pintype "passive"))
      (node (ref "R39") (pin "1") (pinfunction "1_1") (pintype "passive"))
    )
    (net (code "148") (name "Net-(IC1-PD6)") (class "Default")
      (node (ref "IC1") (pin "16") (pinfunction "PD6_16") (pintype "passive"))
      (node (ref "R37") (pin "1") (pinfunction "1_1") (pintype "passive"))
    )
    (net (code "149") (name "Net-(IC1-PD7)") (class "Default")
      (node (ref "IC1") (pin "17") (pinfunction "PD7_17") (pintype "passive"))
      (node (ref "R35") (pin "1") (pinfunction "1_1") (pintype "passive"))
    )
    (net (code "150") (name "Net-(IC1-PD~{1})") (class "Default")
      (node (ref "IC1") (pin "11") (pinfunction "PD~{1}_11") (pintype "passive"))
      (node (ref "R45") (pin "1") (pinfunction "1_1") (pintype "passive"))
    )
    (net (code "151") (name "Net-(IC1-PD~{2})") (class "Default")
      (node (ref "IC1") (pin "12") (pinfunction "PD~{2}_12") (pintype "passive"))
      (node (ref "R44") (pin "1") (pinfunction "1_1") (pintype "passive"))
    )
    (net (code "152") (name "Net-(IC1-PF0)") (class "Default")
      (node (ref "IC1") (pin "20") (pinfunction "PF0_20") (pintype "passive"))
      (node (ref "R34") (pin "1") (pinfunction "1_1") (pintype "passive"))
    )
    (net (code "153") (name "Net-(IC1-PF1)") (class "Default")
      (node (ref "IC1") (pin "21") (pinfunction "PF1_21") (pintype "passive"))
      (node (ref "R32") (pin "1") (pinfunction "1_1") (pintype "passive"))
    )
    (net (code "154") (name "Net-(IC1-PF2)") (class "Default")
      (node (ref "IC1") (pin "22") (pinfunction "PF2_22") (pintype "passive"))
      (node (ref "R30") (pin "1") (pinfunction "1_1") (pintype "passive"))
    )
    (net (code "155") (name "Net-(IC1-PF3)") (class "Default")
      (node (ref "IC1") (pin "23") (pinfunction "PF3_23") (pintype "passive"))
      (node (ref "R28") (pin "1") (pinfunction "1_1") (pintype "passive"))
    )
    (net (code "156") (name "Net-(IC1-PF4)") (class "Default")
      (node (ref "IC1") (pin "24") (pinfunction "PF4_24") (pintype "passive"))
      (node (ref "R26") (pin "1") (pinfunction "1_1") (pintype "passive"))
    )
    (net (code "157") (name "Net-(IC1-PF5)") (class "Default")
      (node (ref "IC1") (pin "25") (pinfunction "PF5_25") (pintype "passive"))
      (node (ref "R22") (pin "1") (pinfunction "1_1") (pintype "passive"))
    )
    (net (code "158") (name "Net-(IC1-PF6_(~{RESET)})") (class "Default")
      (node (ref "IC1") (pin "26") (pinfunction "PF6_(~{RESET)}_26") (pintype "passive"))
      (node (ref "R20") (pin "1") (pinfunction "1_1") (pintype "passive"))
    )
    (net (code "159") (name "Net-(IC1-PF7_(UPDI))") (class "Default")
      (node (ref "IC1") (pin "27") (pinfunction "PF7_(UPDI)_27") (pintype "passive"))
      (node (ref "R18") (pin "1") (pinfunction "1_1") (pintype "passive"))
    )
    (net (code "160") (name "Net-(J1-Pad1)") (class "Default")
      (node (ref "J1") (pin "1") (pinfunction "1_1") (pintype "passive"))
      (node (ref "R24") (pin "1") (pinfunction "1_1") (pintype "passive"))
    )
    (net (code "161") (name "Net-(J2-Pad1)") (class "Default")
      (node (ref "J2") (pin "1") (pinfunction "1_1") (pintype "passive"))
      (node (ref "R23") (pin "1") (pinfunction "1_1") (pintype "passive"))
    )
    (net (code "162") (name "Net-(R4-Pad1)") (class "Default")
      (node (ref "R4") (pin "1") (pinfunction "1_1") (pintype "passive"))
      (node (ref "TP2") (pin "1") (pinfunction "1_1") (pintype "passive"))
    )
    (net (code "163") (name "Net-(R5-Pad2)") (class "Default")
      (node (ref "R5") (pin "2") (pinfunction "2_2") (pintype "passive"))
      (node (ref "TP3") (pin "1") (pinfunction "1_1") (pintype "passive"))
    )
    (net (code "164") (name "Net-(R8-Pad1)") (class "Default")
      (node (ref "R8") (pin "1") (pinfunction "1_1") (pintype "passive"))
      (node (ref "TP4") (pin "1") (pinfunction "1_1") (pintype "passive"))
    )
    (net (code "165") (name "Net-(R34-Pad2)") (class "Default")
      (node (ref "R34") (pin "2") (pinfunction "2_2") (pintype "passive"))
      (node (ref "TP5") (pin "1") (pinfunction "1_1") (pintype "passive"))
    )
    (net (code "166") (name "Net-(R36-Pad1)") (class "Default")
      (node (ref "R36") (pin "1") (pinfunction "1_1") (pintype "passive"))
      (node (ref "TP6") (pin "1") (pinfunction "1_1") (pintype "passive"))
    )
    (net (code "167") (name "Net-(R38-Pad1)") (class "Default")
      (node (ref "R38") (pin "1") (pinfunction "1_1") (pintype "passive"))
      (node (ref "TP7") (pin "1") (pinfunction "1_1") (pintype "passive"))
    )
    (net (code "168") (name "unconnected-(B3-Serial_Out-Pad9)") (class "Default")
      (node (ref "B3") (pin "9") (pinfunction "Serial_Out_9") (pintype "passive+no_connect"))
    )
    (net (code "169") (name "unconnected-(H3-Pad4)") (class "Default")
      (node (ref "H3") (pin "4") (pinfunction "4_4") (pintype "passive+no_connect"))
    )
  )
)
